# BMS_Practice_Board.net
KiCad netlist of a schematic drawn in EAGLE
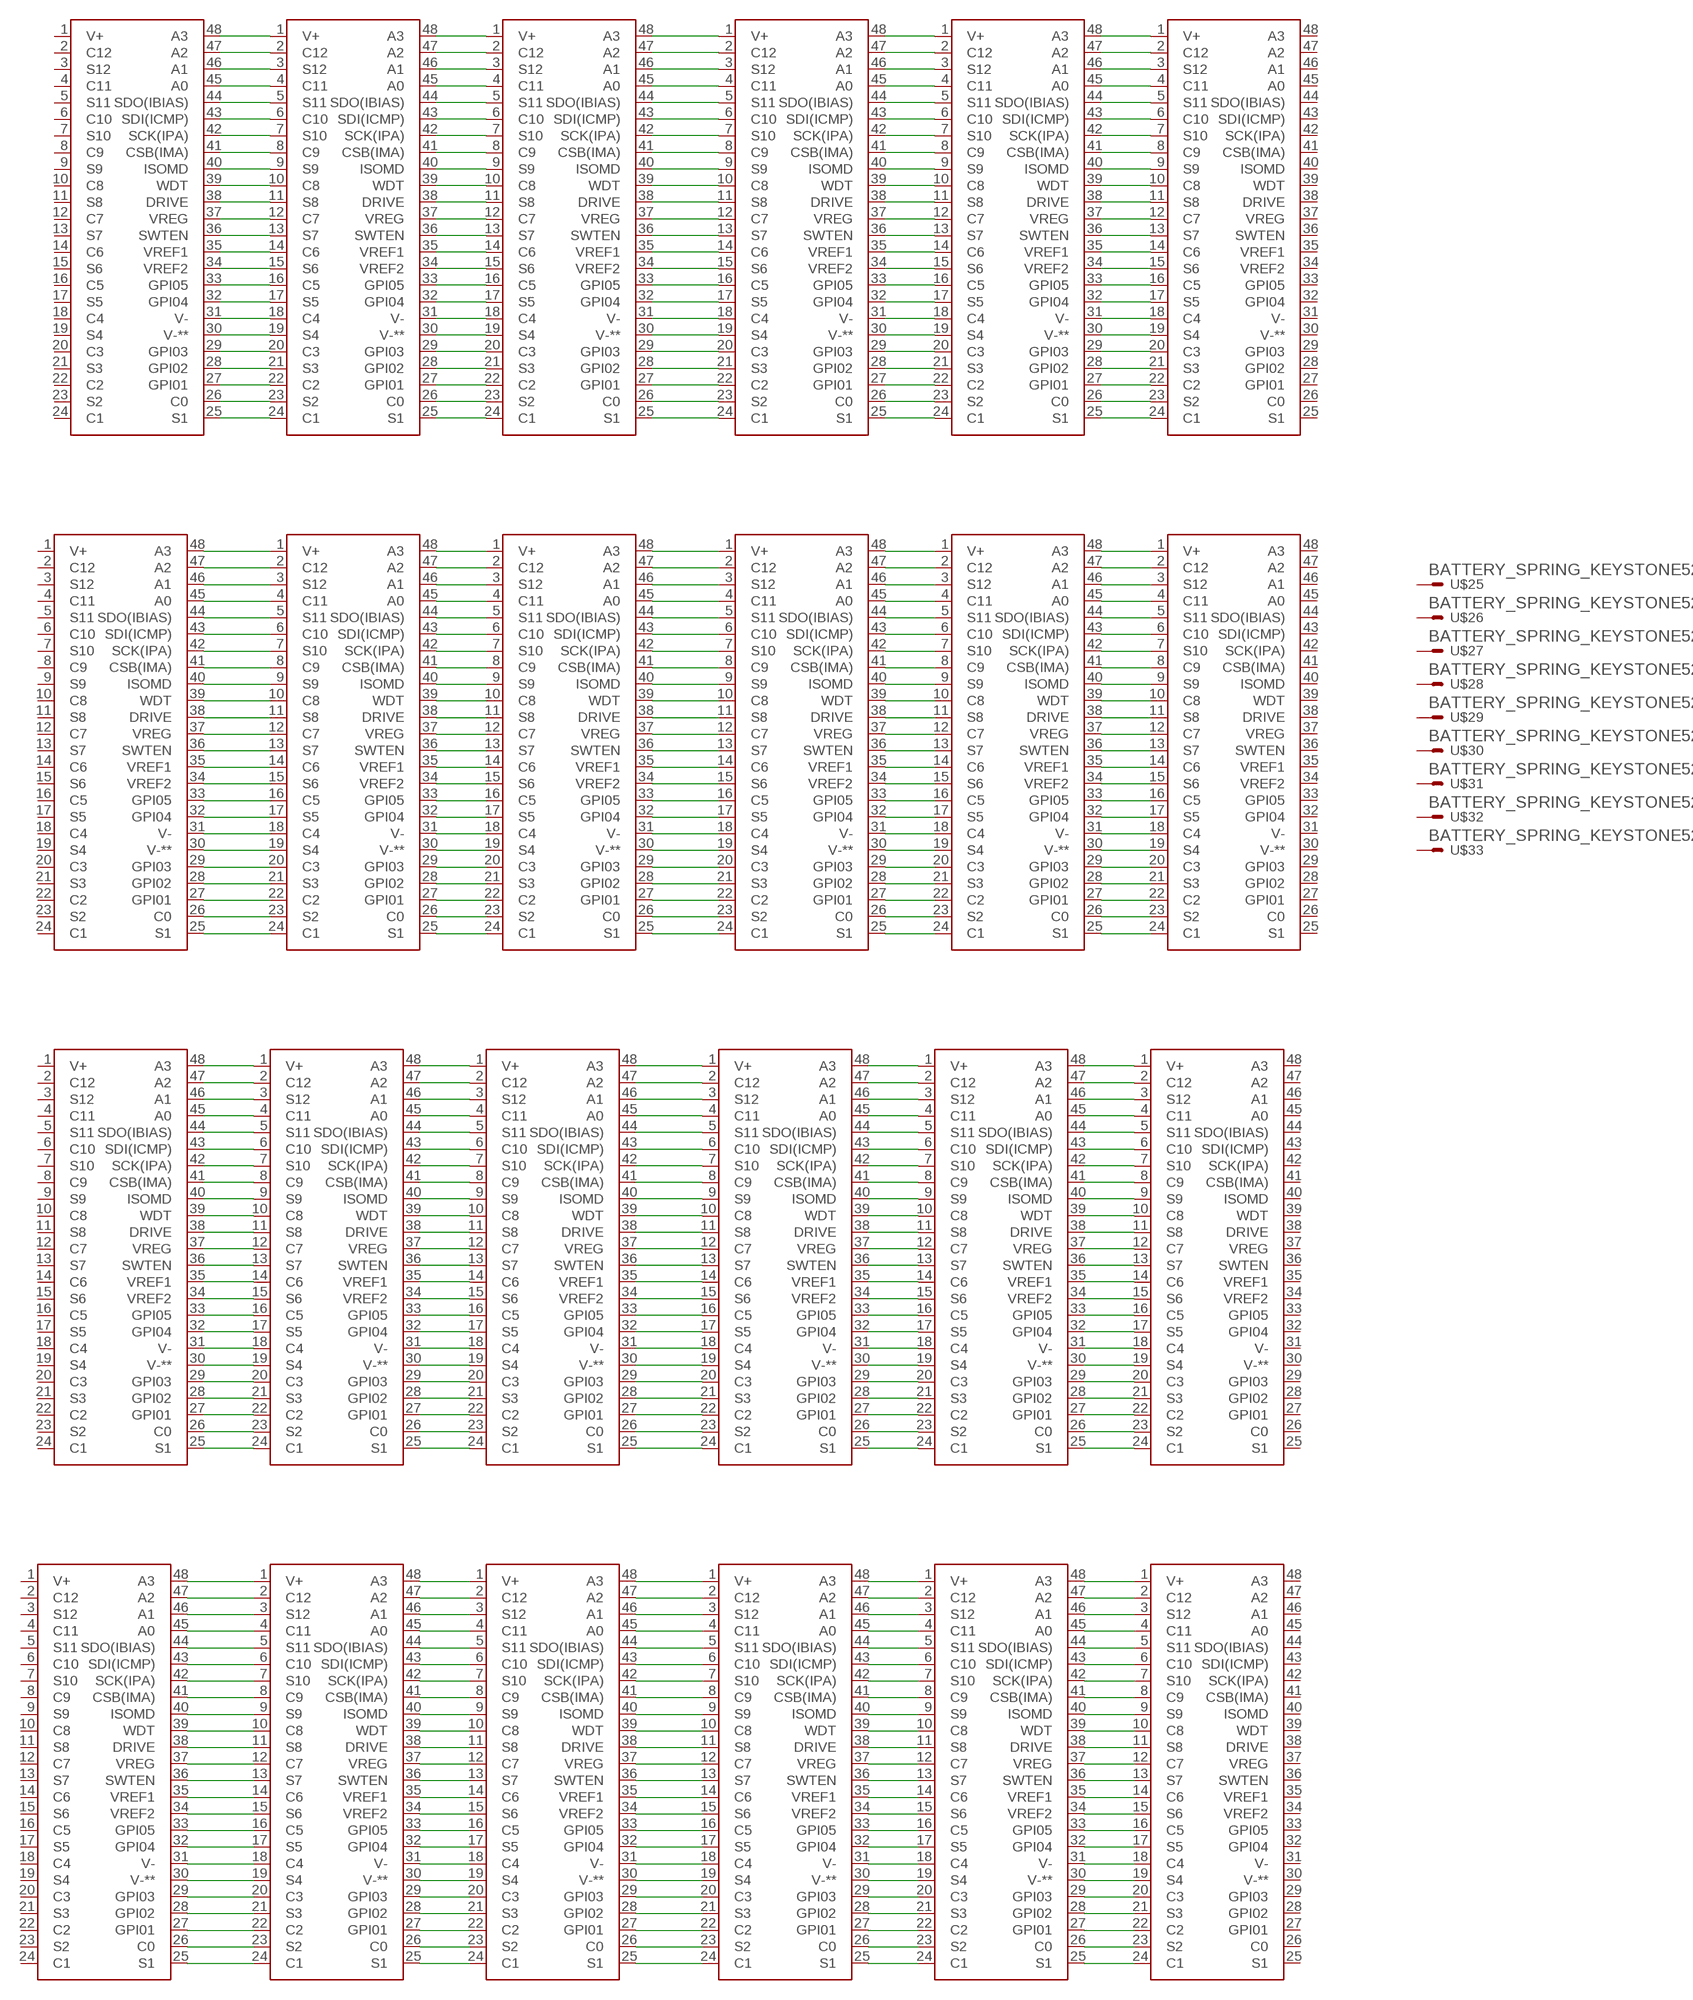
[diagram p0: schematic, sheet 1]

(export (version "E")
  (design (tool "Eeschema 10.0.6"))
  (components
    (comp (ref "U$1")
      (value "LTC6804-2")
      (footprint "eagle-import:LTC6804")
      (libsource (lib "eagle-import") (part "LTC6804-2"))
    )
    (comp (ref "U$2")
      (value "LTC6804-2")
      (footprint "eagle-import:LTC6804")
      (libsource (lib "eagle-import") (part "LTC6804-2"))
    )
    (comp (ref "U$3")
      (value "LTC6804-2")
      (footprint "eagle-import:LTC6804")
      (libsource (lib "eagle-import") (part "LTC6804-2"))
    )
    (comp (ref "U$4")
      (value "LTC6804-2")
      (footprint "eagle-import:LTC6804")
      (libsource (lib "eagle-import") (part "LTC6804-2"))
    )
    (comp (ref "U$5")
      (value "LTC6804-2")
      (footprint "eagle-import:LTC6804")
      (libsource (lib "eagle-import") (part "LTC6804-2"))
    )
    (comp (ref "U$6")
      (value "LTC6804-2")
      (footprint "eagle-import:LTC6804")
      (libsource (lib "eagle-import") (part "LTC6804-2"))
    )
    (comp (ref "U$7")
      (value "LTC6804-2")
      (footprint "eagle-import:LTC6804")
      (libsource (lib "eagle-import") (part "LTC6804-2"))
    )
    (comp (ref "U$8")
      (value "LTC6804-2")
      (footprint "eagle-import:LTC6804")
      (libsource (lib "eagle-import") (part "LTC6804-2"))
    )
    (comp (ref "U$9")
      (value "LTC6804-2")
      (footprint "eagle-import:LTC6804")
      (libsource (lib "eagle-import") (part "LTC6804-2"))
    )
    (comp (ref "U$10")
      (value "LTC6804-2")
      (footprint "eagle-import:LTC6804")
      (libsource (lib "eagle-import") (part "LTC6804-2"))
    )
    (comp (ref "U$11")
      (value "LTC6804-2")
      (footprint "eagle-import:LTC6804")
      (libsource (lib "eagle-import") (part "LTC6804-2"))
    )
    (comp (ref "U$12")
      (value "LTC6804-2")
      (footprint "eagle-import:LTC6804")
      (libsource (lib "eagle-import") (part "LTC6804-2"))
    )
    (comp (ref "U$13")
      (value "LTC6804-2")
      (footprint "eagle-import:LTC6804")
      (libsource (lib "eagle-import") (part "LTC6804-2"))
    )
    (comp (ref "U$14")
      (value "LTC6804-2")
      (footprint "eagle-import:LTC6804")
      (libsource (lib "eagle-import") (part "LTC6804-2"))
    )
    (comp (ref "U$15")
      (value "LTC6804-2")
      (footprint "eagle-import:LTC6804")
      (libsource (lib "eagle-import") (part "LTC6804-2"))
    )
    (comp (ref "U$16")
      (value "LTC6804-2")
      (footprint "eagle-import:LTC6804")
      (libsource (lib "eagle-import") (part "LTC6804-2"))
    )
    (comp (ref "U$17")
      (value "LTC6804-2")
      (footprint "eagle-import:LTC6804")
      (libsource (lib "eagle-import") (part "LTC6804-2"))
    )
    (comp (ref "U$18")
      (value "LTC6804-2")
      (footprint "eagle-import:LTC6804")
      (libsource (lib "eagle-import") (part "LTC6804-2"))
    )
    (comp (ref "U$19")
      (value "LTC6804-2")
      (footprint "eagle-import:LTC6804")
      (libsource (lib "eagle-import") (part "LTC6804-2"))
    )
    (comp (ref "U$20")
      (value "LTC6804-2")
      (footprint "eagle-import:LTC6804")
      (libsource (lib "eagle-import") (part "LTC6804-2"))
    )
    (comp (ref "U$21")
      (value "LTC6804-2")
      (footprint "eagle-import:LTC6804")
      (libsource (lib "eagle-import") (part "LTC6804-2"))
    )
    (comp (ref "U$22")
      (value "LTC6804-2")
      (footprint "eagle-import:LTC6804")
      (libsource (lib "eagle-import") (part "LTC6804-2"))
    )
    (comp (ref "U$23")
      (value "LTC6804-2")
      (footprint "eagle-import:LTC6804")
      (libsource (lib "eagle-import") (part "LTC6804-2"))
    )
    (comp (ref "U$24")
      (value "LTC6804-2")
      (footprint "eagle-import:LTC6804")
      (libsource (lib "eagle-import") (part "LTC6804-2"))
    )
    (comp (ref "U$25")
      (value "BATTERY_SPRING_KEYSTONE5222")
      (footprint "eagle-import:KEYSTONE5222")
      (libsource (lib "eagle-import") (part "BATTERY_SPRING_KEYSTONE5222"))
    )
    (comp (ref "U$26")
      (value "BATTERY_SPRING_KEYSTONE5222")
      (footprint "eagle-import:KEYSTONE5222")
      (libsource (lib "eagle-import") (part "BATTERY_SPRING_KEYSTONE5222"))
    )
    (comp (ref "U$27")
      (value "BATTERY_SPRING_KEYSTONE5222")
      (footprint "eagle-import:KEYSTONE5222")
      (libsource (lib "eagle-import") (part "BATTERY_SPRING_KEYSTONE5222"))
    )
    (comp (ref "U$28")
      (value "BATTERY_SPRING_KEYSTONE5222")
      (footprint "eagle-import:KEYSTONE5222")
      (libsource (lib "eagle-import") (part "BATTERY_SPRING_KEYSTONE5222"))
    )
    (comp (ref "U$29")
      (value "BATTERY_SPRING_KEYSTONE5222")
      (footprint "eagle-import:KEYSTONE5222")
      (libsource (lib "eagle-import") (part "BATTERY_SPRING_KEYSTONE5222"))
    )
    (comp (ref "U$30")
      (value "BATTERY_SPRING_KEYSTONE5222")
      (footprint "eagle-import:KEYSTONE5222")
      (libsource (lib "eagle-import") (part "BATTERY_SPRING_KEYSTONE5222"))
    )
    (comp (ref "U$31")
      (value "BATTERY_SPRING_KEYSTONE5222")
      (footprint "eagle-import:KEYSTONE5222")
      (libsource (lib "eagle-import") (part "BATTERY_SPRING_KEYSTONE5222"))
    )
    (comp (ref "U$32")
      (value "BATTERY_SPRING_KEYSTONE5222")
      (footprint "eagle-import:KEYSTONE5222")
      (libsource (lib "eagle-import") (part "BATTERY_SPRING_KEYSTONE5222"))
    )
    (comp (ref "U$33")
      (value "BATTERY_SPRING_KEYSTONE5222")
      (footprint "eagle-import:KEYSTONE5222")
      (libsource (lib "eagle-import") (part "BATTERY_SPRING_KEYSTONE5222"))
    )
  )
  (nets
    (net (code "1") (name "Net-(U$1-A0)") (class "Default")
      (node (ref "U$1") (pin "45") (pinfunction "A0_45") (pintype "bidirectional"))
      (node (ref "U$2") (pin "4") (pinfunction "C11_4") (pintype "bidirectional"))
    )
    (net (code "2") (name "Net-(U$1-A1)") (class "Default")
      (node (ref "U$1") (pin "46") (pinfunction "A1_46") (pintype "bidirectional"))
      (node (ref "U$2") (pin "3") (pinfunction "S12_3") (pintype "bidirectional"))
    )
    (net (code "3") (name "Net-(U$1-A2)") (class "Default")
      (node (ref "U$1") (pin "47") (pinfunction "A2_47") (pintype "bidirectional"))
      (node (ref "U$2") (pin "2") (pinfunction "C12_2") (pintype "bidirectional"))
    )
    (net (code "4") (name "Net-(U$1-A3)") (class "Default")
      (node (ref "U$1") (pin "48") (pinfunction "A3_48") (pintype "bidirectional"))
      (node (ref "U$2") (pin "1") (pinfunction "V+_1") (pintype "bidirectional"))
    )
    (net (code "5") (name "Net-(U$1-C0)") (class "Default")
      (node (ref "U$1") (pin "26") (pinfunction "C0_26") (pintype "bidirectional"))
      (node (ref "U$2") (pin "23") (pinfunction "S2_23") (pintype "bidirectional"))
    )
    (net (code "6") (name "Net-(U$1-CSB(IMA))") (class "Default")
      (node (ref "U$1") (pin "41") (pinfunction "CSB(IMA)_41") (pintype "bidirectional"))
      (node (ref "U$2") (pin "8") (pinfunction "C9_8") (pintype "bidirectional"))
    )
    (net (code "7") (name "Net-(U$1-DRIVE)") (class "Default")
      (node (ref "U$1") (pin "38") (pinfunction "DRIVE_38") (pintype "bidirectional"))
      (node (ref "U$2") (pin "11") (pinfunction "S8_11") (pintype "bidirectional"))
    )
    (net (code "8") (name "Net-(U$1-GPI01)") (class "Default")
      (node (ref "U$1") (pin "27") (pinfunction "GPI01_27") (pintype "bidirectional"))
      (node (ref "U$2") (pin "22") (pinfunction "C2_22") (pintype "bidirectional"))
    )
    (net (code "9") (name "Net-(U$1-GPI02)") (class "Default")
      (node (ref "U$1") (pin "28") (pinfunction "GPI02_28") (pintype "bidirectional"))
      (node (ref "U$2") (pin "21") (pinfunction "S3_21") (pintype "bidirectional"))
    )
    (net (code "10") (name "Net-(U$1-GPI03)") (class "Default")
      (node (ref "U$1") (pin "29") (pinfunction "GPI03_29") (pintype "bidirectional"))
      (node (ref "U$2") (pin "20") (pinfunction "C3_20") (pintype "bidirectional"))
    )
    (net (code "11") (name "Net-(U$1-GPI04)") (class "Default")
      (node (ref "U$1") (pin "32") (pinfunction "GPI04_32") (pintype "bidirectional"))
      (node (ref "U$2") (pin "17") (pinfunction "S5_17") (pintype "bidirectional"))
    )
    (net (code "12") (name "Net-(U$1-GPI05)") (class "Default")
      (node (ref "U$1") (pin "33") (pinfunction "GPI05_33") (pintype "bidirectional"))
      (node (ref "U$2") (pin "16") (pinfunction "C5_16") (pintype "bidirectional"))
    )
    (net (code "13") (name "Net-(U$1-ISOMD)") (class "Default")
      (node (ref "U$1") (pin "40") (pinfunction "ISOMD_40") (pintype "bidirectional"))
      (node (ref "U$2") (pin "9") (pinfunction "S9_9") (pintype "bidirectional"))
    )
    (net (code "14") (name "Net-(U$1-S1)") (class "Default")
      (node (ref "U$1") (pin "25") (pinfunction "S1_25") (pintype "bidirectional"))
      (node (ref "U$2") (pin "24") (pinfunction "C1_24") (pintype "bidirectional"))
    )
    (net (code "15") (name "Net-(U$1-SCK(IPA))") (class "Default")
      (node (ref "U$1") (pin "42") (pinfunction "SCK(IPA)_42") (pintype "bidirectional"))
      (node (ref "U$2") (pin "7") (pinfunction "S10_7") (pintype "bidirectional"))
    )
    (net (code "16") (name "Net-(U$1-SDI(ICMP))") (class "Default")
      (node (ref "U$1") (pin "43") (pinfunction "SDI(ICMP)_43") (pintype "bidirectional"))
      (node (ref "U$2") (pin "6") (pinfunction "C10_6") (pintype "bidirectional"))
    )
    (net (code "17") (name "Net-(U$1-SDO(IBIAS))") (class "Default")
      (node (ref "U$1") (pin "44") (pinfunction "SDO(IBIAS)_44") (pintype "bidirectional"))
      (node (ref "U$2") (pin "5") (pinfunction "S11_5") (pintype "bidirectional"))
    )
    (net (code "18") (name "Net-(U$1-SWTEN)") (class "Default")
      (node (ref "U$1") (pin "36") (pinfunction "SWTEN_36") (pintype "bidirectional"))
      (node (ref "U$2") (pin "13") (pinfunction "S7_13") (pintype "bidirectional"))
    )
    (net (code "19") (name "Net-(U$1-V-)") (class "Default")
      (node (ref "U$1") (pin "31") (pinfunction "V-_31") (pintype "bidirectional"))
      (node (ref "U$2") (pin "18") (pinfunction "C4_18") (pintype "bidirectional"))
    )
    (net (code "20") (name "Net-(U$1-V-**)") (class "Default")
      (node (ref "U$1") (pin "30") (pinfunction "V-**_30") (pintype "bidirectional"))
      (node (ref "U$2") (pin "19") (pinfunction "S4_19") (pintype "bidirectional"))
    )
    (net (code "21") (name "Net-(U$1-VREF1)") (class "Default")
      (node (ref "U$1") (pin "35") (pinfunction "VREF1_35") (pintype "bidirectional"))
      (node (ref "U$2") (pin "14") (pinfunction "C6_14") (pintype "bidirectional"))
    )
    (net (code "22") (name "Net-(U$1-VREF2)") (class "Default")
      (node (ref "U$1") (pin "34") (pinfunction "VREF2_34") (pintype "bidirectional"))
      (node (ref "U$2") (pin "15") (pinfunction "S6_15") (pintype "bidirectional"))
    )
    (net (code "23") (name "Net-(U$1-VREG)") (class "Default")
      (node (ref "U$1") (pin "37") (pinfunction "VREG_37") (pintype "bidirectional"))
      (node (ref "U$2") (pin "12") (pinfunction "C7_12") (pintype "bidirectional"))
    )
    (net (code "24") (name "Net-(U$1-WDT)") (class "Default")
      (node (ref "U$1") (pin "39") (pinfunction "WDT_39") (pintype "bidirectional"))
      (node (ref "U$2") (pin "10") (pinfunction "C8_10") (pintype "bidirectional"))
    )
    (net (code "25") (name "Net-(U$2-A0)") (class "Default")
      (node (ref "U$2") (pin "45") (pinfunction "A0_45") (pintype "bidirectional"))
      (node (ref "U$3") (pin "4") (pinfunction "C11_4") (pintype "bidirectional"))
    )
    (net (code "26") (name "Net-(U$2-A1)") (class "Default")
      (node (ref "U$2") (pin "46") (pinfunction "A1_46") (pintype "bidirectional"))
      (node (ref "U$3") (pin "3") (pinfunction "S12_3") (pintype "bidirectional"))
    )
    (net (code "27") (name "Net-(U$2-A2)") (class "Default")
      (node (ref "U$2") (pin "47") (pinfunction "A2_47") (pintype "bidirectional"))
      (node (ref "U$3") (pin "2") (pinfunction "C12_2") (pintype "bidirectional"))
    )
    (net (code "28") (name "Net-(U$2-A3)") (class "Default")
      (node (ref "U$2") (pin "48") (pinfunction "A3_48") (pintype "bidirectional"))
      (node (ref "U$3") (pin "1") (pinfunction "V+_1") (pintype "bidirectional"))
    )
    (net (code "29") (name "Net-(U$2-C0)") (class "Default")
      (node (ref "U$2") (pin "26") (pinfunction "C0_26") (pintype "bidirectional"))
      (node (ref "U$3") (pin "23") (pinfunction "S2_23") (pintype "bidirectional"))
    )
    (net (code "30") (name "Net-(U$2-CSB(IMA))") (class "Default")
      (node (ref "U$2") (pin "41") (pinfunction "CSB(IMA)_41") (pintype "bidirectional"))
      (node (ref "U$3") (pin "8") (pinfunction "C9_8") (pintype "bidirectional"))
    )
    (net (code "31") (name "Net-(U$2-DRIVE)") (class "Default")
      (node (ref "U$2") (pin "38") (pinfunction "DRIVE_38") (pintype "bidirectional"))
      (node (ref "U$3") (pin "11") (pinfunction "S8_11") (pintype "bidirectional"))
    )
    (net (code "32") (name "Net-(U$2-GPI01)") (class "Default")
      (node (ref "U$2") (pin "27") (pinfunction "GPI01_27") (pintype "bidirectional"))
      (node (ref "U$3") (pin "22") (pinfunction "C2_22") (pintype "bidirectional"))
    )
    (net (code "33") (name "Net-(U$2-GPI02)") (class "Default")
      (node (ref "U$2") (pin "28") (pinfunction "GPI02_28") (pintype "bidirectional"))
      (node (ref "U$3") (pin "21") (pinfunction "S3_21") (pintype "bidirectional"))
    )
    (net (code "34") (name "Net-(U$2-GPI03)") (class "Default")
      (node (ref "U$2") (pin "29") (pinfunction "GPI03_29") (pintype "bidirectional"))
      (node (ref "U$3") (pin "20") (pinfunction "C3_20") (pintype "bidirectional"))
    )
    (net (code "35") (name "Net-(U$2-GPI04)") (class "Default")
      (node (ref "U$2") (pin "32") (pinfunction "GPI04_32") (pintype "bidirectional"))
      (node (ref "U$3") (pin "17") (pinfunction "S5_17") (pintype "bidirectional"))
    )
    (net (code "36") (name "Net-(U$2-GPI05)") (class "Default")
      (node (ref "U$2") (pin "33") (pinfunction "GPI05_33") (pintype "bidirectional"))
      (node (ref "U$3") (pin "16") (pinfunction "C5_16") (pintype "bidirectional"))
    )
    (net (code "37") (name "Net-(U$2-ISOMD)") (class "Default")
      (node (ref "U$2") (pin "40") (pinfunction "ISOMD_40") (pintype "bidirectional"))
      (node (ref "U$3") (pin "9") (pinfunction "S9_9") (pintype "bidirectional"))
    )
    (net (code "38") (name "Net-(U$2-S1)") (class "Default")
      (node (ref "U$2") (pin "25") (pinfunction "S1_25") (pintype "bidirectional"))
      (node (ref "U$3") (pin "24") (pinfunction "C1_24") (pintype "bidirectional"))
    )
    (net (code "39") (name "Net-(U$2-SCK(IPA))") (class "Default")
      (node (ref "U$2") (pin "42") (pinfunction "SCK(IPA)_42") (pintype "bidirectional"))
      (node (ref "U$3") (pin "7") (pinfunction "S10_7") (pintype "bidirectional"))
    )
    (net (code "40") (name "Net-(U$2-SDI(ICMP))") (class "Default")
      (node (ref "U$2") (pin "43") (pinfunction "SDI(ICMP)_43") (pintype "bidirectional"))
      (node (ref "U$3") (pin "6") (pinfunction "C10_6") (pintype "bidirectional"))
    )
    (net (code "41") (name "Net-(U$2-SDO(IBIAS))") (class "Default")
      (node (ref "U$2") (pin "44") (pinfunction "SDO(IBIAS)_44") (pintype "bidirectional"))
      (node (ref "U$3") (pin "5") (pinfunction "S11_5") (pintype "bidirectional"))
    )
    (net (code "42") (name "Net-(U$2-SWTEN)") (class "Default")
      (node (ref "U$2") (pin "36") (pinfunction "SWTEN_36") (pintype "bidirectional"))
      (node (ref "U$3") (pin "13") (pinfunction "S7_13") (pintype "bidirectional"))
    )
    (net (code "43") (name "Net-(U$2-V-)") (class "Default")
      (node (ref "U$2") (pin "31") (pinfunction "V-_31") (pintype "bidirectional"))
      (node (ref "U$3") (pin "18") (pinfunction "C4_18") (pintype "bidirectional"))
    )
    (net (code "44") (name "Net-(U$2-V-**)") (class "Default")
      (node (ref "U$2") (pin "30") (pinfunction "V-**_30") (pintype "bidirectional"))
      (node (ref "U$3") (pin "19") (pinfunction "S4_19") (pintype "bidirectional"))
    )
    (net (code "45") (name "Net-(U$2-VREF1)") (class "Default")
      (node (ref "U$2") (pin "35") (pinfunction "VREF1_35") (pintype "bidirectional"))
      (node (ref "U$3") (pin "14") (pinfunction "C6_14") (pintype "bidirectional"))
    )
    (net (code "46") (name "Net-(U$2-VREF2)") (class "Default")
      (node (ref "U$2") (pin "34") (pinfunction "VREF2_34") (pintype "bidirectional"))
      (node (ref "U$3") (pin "15") (pinfunction "S6_15") (pintype "bidirectional"))
    )
    (net (code "47") (name "Net-(U$2-VREG)") (class "Default")
      (node (ref "U$2") (pin "37") (pinfunction "VREG_37") (pintype "bidirectional"))
      (node (ref "U$3") (pin "12") (pinfunction "C7_12") (pintype "bidirectional"))
    )
    (net (code "48") (name "Net-(U$2-WDT)") (class "Default")
      (node (ref "U$2") (pin "39") (pinfunction "WDT_39") (pintype "bidirectional"))
      (node (ref "U$3") (pin "10") (pinfunction "C8_10") (pintype "bidirectional"))
    )
    (net (code "49") (name "Net-(U$3-A0)") (class "Default")
      (node (ref "U$3") (pin "45") (pinfunction "A0_45") (pintype "bidirectional"))
      (node (ref "U$4") (pin "4") (pinfunction "C11_4") (pintype "bidirectional"))
    )
    (net (code "50") (name "Net-(U$3-A1)") (class "Default")
      (node (ref "U$3") (pin "46") (pinfunction "A1_46") (pintype "bidirectional"))
      (node (ref "U$4") (pin "3") (pinfunction "S12_3") (pintype "bidirectional"))
    )
    (net (code "51") (name "Net-(U$3-A2)") (class "Default")
      (node (ref "U$3") (pin "47") (pinfunction "A2_47") (pintype "bidirectional"))
      (node (ref "U$4") (pin "2") (pinfunction "C12_2") (pintype "bidirectional"))
    )
    (net (code "52") (name "Net-(U$3-A3)") (class "Default")
      (node (ref "U$3") (pin "48") (pinfunction "A3_48") (pintype "bidirectional"))
      (node (ref "U$4") (pin "1") (pinfunction "V+_1") (pintype "bidirectional"))
    )
    (net (code "53") (name "Net-(U$3-C0)") (class "Default")
      (node (ref "U$3") (pin "26") (pinfunction "C0_26") (pintype "bidirectional"))
      (node (ref "U$4") (pin "23") (pinfunction "S2_23") (pintype "bidirectional"))
    )
    (net (code "54") (name "Net-(U$3-CSB(IMA))") (class "Default")
      (node (ref "U$3") (pin "41") (pinfunction "CSB(IMA)_41") (pintype "bidirectional"))
      (node (ref "U$4") (pin "8") (pinfunction "C9_8") (pintype "bidirectional"))
    )
    (net (code "55") (name "Net-(U$3-DRIVE)") (class "Default")
      (node (ref "U$3") (pin "38") (pinfunction "DRIVE_38") (pintype "bidirectional"))
      (node (ref "U$4") (pin "11") (pinfunction "S8_11") (pintype "bidirectional"))
    )
    (net (code "56") (name "Net-(U$3-GPI01)") (class "Default")
      (node (ref "U$3") (pin "27") (pinfunction "GPI01_27") (pintype "bidirectional"))
      (node (ref "U$4") (pin "22") (pinfunction "C2_22") (pintype "bidirectional"))
    )
    (net (code "57") (name "Net-(U$3-GPI02)") (class "Default")
      (node (ref "U$3") (pin "28") (pinfunction "GPI02_28") (pintype "bidirectional"))
      (node (ref "U$4") (pin "21") (pinfunction "S3_21") (pintype "bidirectional"))
    )
    (net (code "58") (name "Net-(U$3-GPI03)") (class "Default")
      (node (ref "U$3") (pin "29") (pinfunction "GPI03_29") (pintype "bidirectional"))
      (node (ref "U$4") (pin "20") (pinfunction "C3_20") (pintype "bidirectional"))
    )
    (net (code "59") (name "Net-(U$3-GPI04)") (class "Default")
      (node (ref "U$3") (pin "32") (pinfunction "GPI04_32") (pintype "bidirectional"))
      (node (ref "U$4") (pin "17") (pinfunction "S5_17") (pintype "bidirectional"))
    )
    (net (code "60") (name "Net-(U$3-GPI05)") (class "Default")
      (node (ref "U$3") (pin "33") (pinfunction "GPI05_33") (pintype "bidirectional"))
      (node (ref "U$4") (pin "16") (pinfunction "C5_16") (pintype "bidirectional"))
    )
    (net (code "61") (name "Net-(U$3-ISOMD)") (class "Default")
      (node (ref "U$3") (pin "40") (pinfunction "ISOMD_40") (pintype "bidirectional"))
      (node (ref "U$4") (pin "9") (pinfunction "S9_9") (pintype "bidirectional"))
    )
    (net (code "62") (name "Net-(U$3-S1)") (class "Default")
      (node (ref "U$3") (pin "25") (pinfunction "S1_25") (pintype "bidirectional"))
      (node (ref "U$4") (pin "24") (pinfunction "C1_24") (pintype "bidirectional"))
    )
    (net (code "63") (name "Net-(U$3-SCK(IPA))") (class "Default")
      (node (ref "U$3") (pin "42") (pinfunction "SCK(IPA)_42") (pintype "bidirectional"))
      (node (ref "U$4") (pin "7") (pinfunction "S10_7") (pintype "bidirectional"))
    )
    (net (code "64") (name "Net-(U$3-SDI(ICMP))") (class "Default")
      (node (ref "U$3") (pin "43") (pinfunction "SDI(ICMP)_43") (pintype "bidirectional"))
      (node (ref "U$4") (pin "6") (pinfunction "C10_6") (pintype "bidirectional"))
    )
    (net (code "65") (name "Net-(U$3-SDO(IBIAS))") (class "Default")
      (node (ref "U$3") (pin "44") (pinfunction "SDO(IBIAS)_44") (pintype "bidirectional"))
      (node (ref "U$4") (pin "5") (pinfunction "S11_5") (pintype "bidirectional"))
    )
    (net (code "66") (name "Net-(U$3-SWTEN)") (class "Default")
      (node (ref "U$3") (pin "36") (pinfunction "SWTEN_36") (pintype "bidirectional"))
      (node (ref "U$4") (pin "13") (pinfunction "S7_13") (pintype "bidirectional"))
    )
    (net (code "67") (name "Net-(U$3-V-)") (class "Default")
      (node (ref "U$3") (pin "31") (pinfunction "V-_31") (pintype "bidirectional"))
      (node (ref "U$4") (pin "18") (pinfunction "C4_18") (pintype "bidirectional"))
    )
    (net (code "68") (name "Net-(U$3-V-**)") (class "Default")
      (node (ref "U$3") (pin "30") (pinfunction "V-**_30") (pintype "bidirectional"))
      (node (ref "U$4") (pin "19") (pinfunction "S4_19") (pintype "bidirectional"))
    )
    (net (code "69") (name "Net-(U$3-VREF1)") (class "Default")
      (node (ref "U$3") (pin "35") (pinfunction "VREF1_35") (pintype "bidirectional"))
      (node (ref "U$4") (pin "14") (pinfunction "C6_14") (pintype "bidirectional"))
    )
    (net (code "70") (name "Net-(U$3-VREF2)") (class "Default")
      (node (ref "U$3") (pin "34") (pinfunction "VREF2_34") (pintype "bidirectional"))
      (node (ref "U$4") (pin "15") (pinfunction "S6_15") (pintype "bidirectional"))
    )
    (net (code "71") (name "Net-(U$3-VREG)") (class "Default")
      (node (ref "U$3") (pin "37") (pinfunction "VREG_37") (pintype "bidirectional"))
      (node (ref "U$4") (pin "12") (pinfunction "C7_12") (pintype "bidirectional"))
    )
    (net (code "72") (name "Net-(U$3-WDT)") (class "Default")
      (node (ref "U$3") (pin "39") (pinfunction "WDT_39") (pintype "bidirectional"))
      (node (ref "U$4") (pin "10") (pinfunction "C8_10") (pintype "bidirectional"))
    )
    (net (code "73") (name "Net-(U$4-A0)") (class "Default")
      (node (ref "U$4") (pin "45") (pinfunction "A0_45") (pintype "bidirectional"))
      (node (ref "U$5") (pin "4") (pinfunction "C11_4") (pintype "bidirectional"))
    )
    (net (code "74") (name "Net-(U$4-A1)") (class "Default")
      (node (ref "U$4") (pin "46") (pinfunction "A1_46") (pintype "bidirectional"))
      (node (ref "U$5") (pin "3") (pinfunction "S12_3") (pintype "bidirectional"))
    )
    (net (code "75") (name "Net-(U$4-A2)") (class "Default")
      (node (ref "U$4") (pin "47") (pinfunction "A2_47") (pintype "bidirectional"))
      (node (ref "U$5") (pin "2") (pinfunction "C12_2") (pintype "bidirectional"))
    )
    (net (code "76") (name "Net-(U$4-A3)") (class "Default")
      (node (ref "U$4") (pin "48") (pinfunction "A3_48") (pintype "bidirectional"))
      (node (ref "U$5") (pin "1") (pinfunction "V+_1") (pintype "bidirectional"))
    )
    (net (code "77") (name "Net-(U$4-C0)") (class "Default")
      (node (ref "U$4") (pin "26") (pinfunction "C0_26") (pintype "bidirectional"))
      (node (ref "U$5") (pin "23") (pinfunction "S2_23") (pintype "bidirectional"))
    )
    (net (code "78") (name "Net-(U$4-CSB(IMA))") (class "Default")
      (node (ref "U$4") (pin "41") (pinfunction "CSB(IMA)_41") (pintype "bidirectional"))
      (node (ref "U$5") (pin "8") (pinfunction "C9_8") (pintype "bidirectional"))
    )
    (net (code "79") (name "Net-(U$4-DRIVE)") (class "Default")
      (node (ref "U$4") (pin "38") (pinfunction "DRIVE_38") (pintype "bidirectional"))
      (node (ref "U$5") (pin "11") (pinfunction "S8_11") (pintype "bidirectional"))
    )
    (net (code "80") (name "Net-(U$4-GPI01)") (class "Default")
      (node (ref "U$4") (pin "27") (pinfunction "GPI01_27") (pintype "bidirectional"))
      (node (ref "U$5") (pin "22") (pinfunction "C2_22") (pintype "bidirectional"))
    )
    (net (code "81") (name "Net-(U$4-GPI02)") (class "Default")
      (node (ref "U$4") (pin "28") (pinfunction "GPI02_28") (pintype "bidirectional"))
      (node (ref "U$5") (pin "21") (pinfunction "S3_21") (pintype "bidirectional"))
    )
    (net (code "82") (name "Net-(U$4-GPI03)") (class "Default")
      (node (ref "U$4") (pin "29") (pinfunction "GPI03_29") (pintype "bidirectional"))
      (node (ref "U$5") (pin "20") (pinfunction "C3_20") (pintype "bidirectional"))
    )
    (net (code "83") (name "Net-(U$4-GPI04)") (class "Default")
      (node (ref "U$4") (pin "32") (pinfunction "GPI04_32") (pintype "bidirectional"))
      (node (ref "U$5") (pin "17") (pinfunction "S5_17") (pintype "bidirectional"))
    )
    (net (code "84") (name "Net-(U$4-GPI05)") (class "Default")
      (node (ref "U$4") (pin "33") (pinfunction "GPI05_33") (pintype "bidirectional"))
      (node (ref "U$5") (pin "16") (pinfunction "C5_16") (pintype "bidirectional"))
    )
    (net (code "85") (name "Net-(U$4-ISOMD)") (class "Default")
      (node (ref "U$4") (pin "40") (pinfunction "ISOMD_40") (pintype "bidirectional"))
      (node (ref "U$5") (pin "9") (pinfunction "S9_9") (pintype "bidirectional"))
    )
    (net (code "86") (name "Net-(U$4-S1)") (class "Default")
      (node (ref "U$4") (pin "25") (pinfunction "S1_25") (pintype "bidirectional"))
      (node (ref "U$5") (pin "24") (pinfunction "C1_24") (pintype "bidirectional"))
    )
    (net (code "87") (name "Net-(U$4-SCK(IPA))") (class "Default")
      (node (ref "U$4") (pin "42") (pinfunction "SCK(IPA)_42") (pintype "bidirectional"))
      (node (ref "U$5") (pin "7") (pinfunction "S10_7") (pintype "bidirectional"))
    )
    (net (code "88") (name "Net-(U$4-SDI(ICMP))") (class "Default")
      (node (ref "U$4") (pin "43") (pinfunction "SDI(ICMP)_43") (pintype "bidirectional"))
      (node (ref "U$5") (pin "6") (pinfunction "C10_6") (pintype "bidirectional"))
    )
    (net (code "89") (name "Net-(U$4-SDO(IBIAS))") (class "Default")
      (node (ref "U$4") (pin "44") (pinfunction "SDO(IBIAS)_44") (pintype "bidirectional"))
      (node (ref "U$5") (pin "5") (pinfunction "S11_5") (pintype "bidirectional"))
    )
    (net (code "90") (name "Net-(U$4-SWTEN)") (class "Default")
      (node (ref "U$4") (pin "36") (pinfunction "SWTEN_36") (pintype "bidirectional"))
      (node (ref "U$5") (pin "13") (pinfunction "S7_13") (pintype "bidirectional"))
    )
    (net (code "91") (name "Net-(U$4-V-)") (class "Default")
      (node (ref "U$4") (pin "31") (pinfunction "V-_31") (pintype "bidirectional"))
      (node (ref "U$5") (pin "18") (pinfunction "C4_18") (pintype "bidirectional"))
    )
    (net (code "92") (name "Net-(U$4-V-**)") (class "Default")
      (node (ref "U$4") (pin "30") (pinfunction "V-**_30") (pintype "bidirectional"))
      (node (ref "U$5") (pin "19") (pinfunction "S4_19") (pintype "bidirectional"))
    )
    (net (code "93") (name "Net-(U$4-VREF1)") (class "Default")
      (node (ref "U$4") (pin "35") (pinfunction "VREF1_35") (pintype "bidirectional"))
      (node (ref "U$5") (pin "14") (pinfunction "C6_14") (pintype "bidirectional"))
    )
    (net (code "94") (name "Net-(U$4-VREF2)") (class "Default")
      (node (ref "U$4") (pin "34") (pinfunction "VREF2_34") (pintype "bidirectional"))
      (node (ref "U$5") (pin "15") (pinfunction "S6_15") (pintype "bidirectional"))
    )
    (net (code "95") (name "Net-(U$4-VREG)") (class "Default")
      (node (ref "U$4") (pin "37") (pinfunction "VREG_37") (pintype "bidirectional"))
      (node (ref "U$5") (pin "12") (pinfunction "C7_12") (pintype "bidirectional"))
    )
    (net (code "96") (name "Net-(U$4-WDT)") (class "Default")
      (node (ref "U$4") (pin "39") (pinfunction "WDT_39") (pintype "bidirectional"))
      (node (ref "U$5") (pin "10") (pinfunction "C8_10") (pintype "bidirectional"))
    )
    (net (code "97") (name "Net-(U$5-A0)") (class "Default")
      (node (ref "U$5") (pin "45") (pinfunction "A0_45") (pintype "bidirectional"))
      (node (ref "U$6") (pin "4") (pinfunction "C11_4") (pintype "bidirectional"))
    )
    (net (code "98") (name "Net-(U$5-A1)") (class "Default")
      (node (ref "U$5") (pin "46") (pinfunction "A1_46") (pintype "bidirectional"))
      (node (ref "U$6") (pin "3") (pinfunction "S12_3") (pintype "bidirectional"))
    )
    (net (code "99") (name "Net-(U$5-A2)") (class "Default")
      (node (ref "U$5") (pin "47") (pinfunction "A2_47") (pintype "bidirectional"))
      (node (ref "U$6") (pin "2") (pinfunction "C12_2") (pintype "bidirectional"))
    )
    (net (code "100") (name "Net-(U$5-A3)") (class "Default")
      (node (ref "U$5") (pin "48") (pinfunction "A3_48") (pintype "bidirectional"))
      (node (ref "U$6") (pin "1") (pinfunction "V+_1") (pintype "bidirectional"))
    )
    (net (code "101") (name "Net-(U$5-C0)") (class "Default")
      (node (ref "U$5") (pin "26") (pinfunction "C0_26") (pintype "bidirectional"))
      (node (ref "U$6") (pin "23") (pinfunction "S2_23") (pintype "bidirectional"))
    )
    (net (code "102") (name "Net-(U$5-CSB(IMA))") (class "Default")
      (node (ref "U$5") (pin "41") (pinfunction "CSB(IMA)_41") (pintype "bidirectional"))
      (node (ref "U$6") (pin "8") (pinfunction "C9_8") (pintype "bidirectional"))
    )
    (net (code "103") (name "Net-(U$5-DRIVE)") (class "Default")
      (node (ref "U$5") (pin "38") (pinfunction "DRIVE_38") (pintype "bidirectional"))
      (node (ref "U$6") (pin "11") (pinfunction "S8_11") (pintype "bidirectional"))
    )
    (net (code "104") (name "Net-(U$5-GPI01)") (class "Default")
      (node (ref "U$5") (pin "27") (pinfunction "GPI01_27") (pintype "bidirectional"))
      (node (ref "U$6") (pin "22") (pinfunction "C2_22") (pintype "bidirectional"))
    )
    (net (code "105") (name "Net-(U$5-GPI02)") (class "Default")
      (node (ref "U$5") (pin "28") (pinfunction "GPI02_28") (pintype "bidirectional"))
      (node (ref "U$6") (pin "21") (pinfunction "S3_21") (pintype "bidirectional"))
    )
    (net (code "106") (name "Net-(U$5-GPI03)") (class "Default")
      (node (ref "U$5") (pin "29") (pinfunction "GPI03_29") (pintype "bidirectional"))
      (node (ref "U$6") (pin "20") (pinfunction "C3_20") (pintype "bidirectional"))
    )
    (net (code "107") (name "Net-(U$5-GPI04)") (class "Default")
      (node (ref "U$5") (pin "32") (pinfunction "GPI04_32") (pintype "bidirectional"))
      (node (ref "U$6") (pin "17") (pinfunction "S5_17") (pintype "bidirectional"))
    )
    (net (code "108") (name "Net-(U$5-GPI05)") (class "Default")
      (node (ref "U$5") (pin "33") (pinfunction "GPI05_33") (pintype "bidirectional"))
      (node (ref "U$6") (pin "16") (pinfunction "C5_16") (pintype "bidirectional"))
    )
    (net (code "109") (name "Net-(U$5-ISOMD)") (class "Default")
      (node (ref "U$5") (pin "40") (pinfunction "ISOMD_40") (pintype "bidirectional"))
      (node (ref "U$6") (pin "9") (pinfunction "S9_9") (pintype "bidirectional"))
    )
    (net (code "110") (name "Net-(U$5-S1)") (class "Default")
      (node (ref "U$5") (pin "25") (pinfunction "S1_25") (pintype "bidirectional"))
      (node (ref "U$6") (pin "24") (pinfunction "C1_24") (pintype "bidirectional"))
    )
    (net (code "111") (name "Net-(U$5-SCK(IPA))") (class "Default")
      (node (ref "U$5") (pin "42") (pinfunction "SCK(IPA)_42") (pintype "bidirectional"))
      (node (ref "U$6") (pin "7") (pinfunction "S10_7") (pintype "bidirectional"))
    )
    (net (code "112") (name "Net-(U$5-SDI(ICMP))") (class "Default")
      (node (ref "U$5") (pin "43") (pinfunction "SDI(ICMP)_43") (pintype "bidirectional"))
      (node (ref "U$6") (pin "6") (pinfunction "C10_6") (pintype "bidirectional"))
    )
    (net (code "113") (name "Net-(U$5-SDO(IBIAS))") (class "Default")
      (node (ref "U$5") (pin "44") (pinfunction "SDO(IBIAS)_44") (pintype "bidirectional"))
      (node (ref "U$6") (pin "5") (pinfunction "S11_5") (pintype "bidirectional"))
    )
    (net (code "114") (name "Net-(U$5-SWTEN)") (class "Default")
      (node (ref "U$5") (pin "36") (pinfunction "SWTEN_36") (pintype "bidirectional"))
      (node (ref "U$6") (pin "13") (pinfunction "S7_13") (pintype "bidirectional"))
    )
    (net (code "115") (name "Net-(U$5-V-)") (class "Default")
      (node (ref "U$5") (pin "31") (pinfunction "V-_31") (pintype "bidirectional"))
      (node (ref "U$6") (pin "18") (pinfunction "C4_18") (pintype "bidirectional"))
    )
    (net (code "116") (name "Net-(U$5-V-**)") (class "Default")
      (node (ref "U$5") (pin "30") (pinfunction "V-**_30") (pintype "bidirectional"))
      (node (ref "U$6") (pin "19") (pinfunction "S4_19") (pintype "bidirectional"))
    )
    (net (code "117") (name "Net-(U$5-VREF1)") (class "Default")
      (node (ref "U$5") (pin "35") (pinfunction "VREF1_35") (pintype "bidirectional"))
      (node (ref "U$6") (pin "14") (pinfunction "C6_14") (pintype "bidirectional"))
    )
    (net (code "118") (name "Net-(U$5-VREF2)") (class "Default")
      (node (ref "U$5") (pin "34") (pinfunction "VREF2_34") (pintype "bidirectional"))
      (node (ref "U$6") (pin "15") (pinfunction "S6_15") (pintype "bidirectional"))
    )
    (net (code "119") (name "Net-(U$5-VREG)") (class "Default")
      (node (ref "U$5") (pin "37") (pinfunction "VREG_37") (pintype "bidirectional"))
      (node (ref "U$6") (pin "12") (pinfunction "C7_12") (pintype "bidirectional"))
    )
    (net (code "120") (name "Net-(U$5-WDT)") (class "Default")
      (node (ref "U$5") (pin "39") (pinfunction "WDT_39") (pintype "bidirectional"))
      (node (ref "U$6") (pin "10") (pinfunction "C8_10") (pintype "bidirectional"))
    )
    (net (code "121") (name "Net-(U$7-A0)") (class "Default")
      (node (ref "U$7") (pin "45") (pinfunction "A0_45") (pintype "bidirectional"))
      (node (ref "U$8") (pin "4") (pinfunction "C11_4") (pintype "bidirectional"))
    )
    (net (code "122") (name "Net-(U$7-A1)") (class "Default")
      (node (ref "U$7") (pin "46") (pinfunction "A1_46") (pintype "bidirectional"))
      (node (ref "U$8") (pin "3") (pinfunction "S12_3") (pintype "bidirectional"))
    )
    (net (code "123") (name "Net-(U$7-A2)") (class "Default")
      (node (ref "U$7") (pin "47") (pinfunction "A2_47") (pintype "bidirectional"))
      (node (ref "U$8") (pin "2") (pinfunction "C12_2") (pintype "bidirectional"))
    )
    (net (code "124") (name "Net-(U$7-A3)") (class "Default")
      (node (ref "U$7") (pin "48") (pinfunction "A3_48") (pintype "bidirectional"))
      (node (ref "U$8") (pin "1") (pinfunction "V+_1") (pintype "bidirectional"))
    )
    (net (code "125") (name "Net-(U$7-C0)") (class "Default")
      (node (ref "U$7") (pin "26") (pinfunction "C0_26") (pintype "bidirectional"))
      (node (ref "U$8") (pin "23") (pinfunction "S2_23") (pintype "bidirectional"))
    )
    (net (code "126") (name "Net-(U$7-CSB(IMA))") (class "Default")
      (node (ref "U$7") (pin "41") (pinfunction "CSB(IMA)_41") (pintype "bidirectional"))
      (node (ref "U$8") (pin "8") (pinfunction "C9_8") (pintype "bidirectional"))
    )
    (net (code "127") (name "Net-(U$7-DRIVE)") (class "Default")
      (node (ref "U$7") (pin "38") (pinfunction "DRIVE_38") (pintype "bidirectional"))
      (node (ref "U$8") (pin "11") (pinfunction "S8_11") (pintype "bidirectional"))
    )
    (net (code "128") (name "Net-(U$7-GPI01)") (class "Default")
      (node (ref "U$7") (pin "27") (pinfunction "GPI01_27") (pintype "bidirectional"))
      (node (ref "U$8") (pin "22") (pinfunction "C2_22") (pintype "bidirectional"))
    )
    (net (code "129") (name "Net-(U$7-GPI02)") (class "Default")
      (node (ref "U$7") (pin "28") (pinfunction "GPI02_28") (pintype "bidirectional"))
      (node (ref "U$8") (pin "21") (pinfunction "S3_21") (pintype "bidirectional"))
    )
    (net (code "130") (name "Net-(U$7-GPI03)") (class "Default")
      (node (ref "U$7") (pin "29") (pinfunction "GPI03_29") (pintype "bidirectional"))
      (node (ref "U$8") (pin "20") (pinfunction "C3_20") (pintype "bidirectional"))
    )
    (net (code "131") (name "Net-(U$7-GPI04)") (class "Default")
      (node (ref "U$7") (pin "32") (pinfunction "GPI04_32") (pintype "bidirectional"))
      (node (ref "U$8") (pin "17") (pinfunction "S5_17") (pintype "bidirectional"))
    )
    (net (code "132") (name "Net-(U$7-GPI05)") (class "Default")
      (node (ref "U$7") (pin "33") (pinfunction "GPI05_33") (pintype "bidirectional"))
      (node (ref "U$8") (pin "16") (pinfunction "C5_16") (pintype "bidirectional"))
    )
    (net (code "133") (name "Net-(U$7-ISOMD)") (class "Default")
      (node (ref "U$7") (pin "40") (pinfunction "ISOMD_40") (pintype "bidirectional"))
      (node (ref "U$8") (pin "9") (pinfunction "S9_9") (pintype "bidirectional"))
    )
    (net (code "134") (name "Net-(U$7-S1)") (class "Default")
      (node (ref "U$7") (pin "25") (pinfunction "S1_25") (pintype "bidirectional"))
      (node (ref "U$8") (pin "24") (pinfunction "C1_24") (pintype "bidirectional"))
    )
    (net (code "135") (name "Net-(U$7-SCK(IPA))") (class "Default")
      (node (ref "U$7") (pin "42") (pinfunction "SCK(IPA)_42") (pintype "bidirectional"))
      (node (ref "U$8") (pin "7") (pinfunction "S10_7") (pintype "bidirectional"))
    )
    (net (code "136") (name "Net-(U$7-SDI(ICMP))") (class "Default")
      (node (ref "U$7") (pin "43") (pinfunction "SDI(ICMP)_43") (pintype "bidirectional"))
      (node (ref "U$8") (pin "6") (pinfunction "C10_6") (pintype "bidirectional"))
    )
    (net (code "137") (name "Net-(U$7-SDO(IBIAS))") (class "Default")
      (node (ref "U$7") (pin "44") (pinfunction "SDO(IBIAS)_44") (pintype "bidirectional"))
      (node (ref "U$8") (pin "5") (pinfunction "S11_5") (pintype "bidirectional"))
    )
    (net (code "138") (name "Net-(U$7-SWTEN)") (class "Default")
      (node (ref "U$7") (pin "36") (pinfunction "SWTEN_36") (pintype "bidirectional"))
      (node (ref "U$8") (pin "13") (pinfunction "S7_13") (pintype "bidirectional"))
    )
    (net (code "139") (name "Net-(U$7-V-)") (class "Default")
      (node (ref "U$7") (pin "31") (pinfunction "V-_31") (pintype "bidirectional"))
      (node (ref "U$8") (pin "18") (pinfunction "C4_18") (pintype "bidirectional"))
    )
    (net (code "140") (name "Net-(U$7-V-**)") (class "Default")
      (node (ref "U$7") (pin "30") (pinfunction "V-**_30") (pintype "bidirectional"))
      (node (ref "U$8") (pin "19") (pinfunction "S4_19") (pintype "bidirectional"))
    )
    (net (code "141") (name "Net-(U$7-VREF1)") (class "Default")
      (node (ref "U$7") (pin "35") (pinfunction "VREF1_35") (pintype "bidirectional"))
      (node (ref "U$8") (pin "14") (pinfunction "C6_14") (pintype "bidirectional"))
    )
    (net (code "142") (name "Net-(U$7-VREF2)") (class "Default")
      (node (ref "U$7") (pin "34") (pinfunction "VREF2_34") (pintype "bidirectional"))
      (node (ref "U$8") (pin "15") (pinfunction "S6_15") (pintype "bidirectional"))
    )
    (net (code "143") (name "Net-(U$7-VREG)") (class "Default")
      (node (ref "U$7") (pin "37") (pinfunction "VREG_37") (pintype "bidirectional"))
      (node (ref "U$8") (pin "12") (pinfunction "C7_12") (pintype "bidirectional"))
    )
    (net (code "144") (name "Net-(U$7-WDT)") (class "Default")
      (node (ref "U$7") (pin "39") (pinfunction "WDT_39") (pintype "bidirectional"))
      (node (ref "U$8") (pin "10") (pinfunction "C8_10") (pintype "bidirectional"))
    )
    (net (code "145") (name "Net-(U$8-A0)") (class "Default")
      (node (ref "U$8") (pin "45") (pinfunction "A0_45") (pintype "bidirectional"))
      (node (ref "U$9") (pin "4") (pinfunction "C11_4") (pintype "bidirectional"))
    )
    (net (code "146") (name "Net-(U$8-A1)") (class "Default")
      (node (ref "U$8") (pin "46") (pinfunction "A1_46") (pintype "bidirectional"))
      (node (ref "U$9") (pin "3") (pinfunction "S12_3") (pintype "bidirectional"))
    )
    (net (code "147") (name "Net-(U$8-A2)") (class "Default")
      (node (ref "U$8") (pin "47") (pinfunction "A2_47") (pintype "bidirectional"))
      (node (ref "U$9") (pin "2") (pinfunction "C12_2") (pintype "bidirectional"))
    )
    (net (code "148") (name "Net-(U$8-A3)") (class "Default")
      (node (ref "U$8") (pin "48") (pinfunction "A3_48") (pintype "bidirectional"))
      (node (ref "U$9") (pin "1") (pinfunction "V+_1") (pintype "bidirectional"))
    )
    (net (code "149") (name "Net-(U$8-C0)") (class "Default")
      (node (ref "U$8") (pin "26") (pinfunction "C0_26") (pintype "bidirectional"))
      (node (ref "U$9") (pin "23") (pinfunction "S2_23") (pintype "bidirectional"))
    )
    (net (code "150") (name "Net-(U$8-CSB(IMA))") (class "Default")
      (node (ref "U$8") (pin "41") (pinfunction "CSB(IMA)_41") (pintype "bidirectional"))
      (node (ref "U$9") (pin "8") (pinfunction "C9_8") (pintype "bidirectional"))
    )
    (net (code "151") (name "Net-(U$8-DRIVE)") (class "Default")
      (node (ref "U$8") (pin "38") (pinfunction "DRIVE_38") (pintype "bidirectional"))
      (node (ref "U$9") (pin "11") (pinfunction "S8_11") (pintype "bidirectional"))
    )
    (net (code "152") (name "Net-(U$8-GPI01)") (class "Default")
      (node (ref "U$8") (pin "27") (pinfunction "GPI01_27") (pintype "bidirectional"))
      (node (ref "U$9") (pin "22") (pinfunction "C2_22") (pintype "bidirectional"))
    )
    (net (code "153") (name "Net-(U$8-GPI02)") (class "Default")
      (node (ref "U$8") (pin "28") (pinfunction "GPI02_28") (pintype "bidirectional"))
      (node (ref "U$9") (pin "21") (pinfunction "S3_21") (pintype "bidirectional"))
    )
    (net (code "154") (name "Net-(U$8-GPI03)") (class "Default")
      (node (ref "U$8") (pin "29") (pinfunction "GPI03_29") (pintype "bidirectional"))
      (node (ref "U$9") (pin "20") (pinfunction "C3_20") (pintype "bidirectional"))
    )
    (net (code "155") (name "Net-(U$8-GPI04)") (class "Default")
      (node (ref "U$8") (pin "32") (pinfunction "GPI04_32") (pintype "bidirectional"))
      (node (ref "U$9") (pin "17") (pinfunction "S5_17") (pintype "bidirectional"))
    )
    (net (code "156") (name "Net-(U$8-GPI05)") (class "Default")
      (node (ref "U$8") (pin "33") (pinfunction "GPI05_33") (pintype "bidirectional"))
      (node (ref "U$9") (pin "16") (pinfunction "C5_16") (pintype "bidirectional"))
    )
    (net (code "157") (name "Net-(U$8-ISOMD)") (class "Default")
      (node (ref "U$8") (pin "40") (pinfunction "ISOMD_40") (pintype "bidirectional"))
      (node (ref "U$9") (pin "9") (pinfunction "S9_9") (pintype "bidirectional"))
    )
    (net (code "158") (name "Net-(U$8-S1)") (class "Default")
      (node (ref "U$8") (pin "25") (pinfunction "S1_25") (pintype "bidirectional"))
      (node (ref "U$9") (pin "24") (pinfunction "C1_24") (pintype "bidirectional"))
    )
    (net (code "159") (name "Net-(U$8-SCK(IPA))") (class "Default")
      (node (ref "U$8") (pin "42") (pinfunction "SCK(IPA)_42") (pintype "bidirectional"))
      (node (ref "U$9") (pin "7") (pinfunction "S10_7") (pintype "bidirectional"))
    )
    (net (code "160") (name "Net-(U$8-SDI(ICMP))") (class "Default")
      (node (ref "U$8") (pin "43") (pinfunction "SDI(ICMP)_43") (pintype "bidirectional"))
      (node (ref "U$9") (pin "6") (pinfunction "C10_6") (pintype "bidirectional"))
    )
    (net (code "161") (name "Net-(U$8-SDO(IBIAS))") (class "Default")
      (node (ref "U$8") (pin "44") (pinfunction "SDO(IBIAS)_44") (pintype "bidirectional"))
      (node (ref "U$9") (pin "5") (pinfunction "S11_5") (pintype "bidirectional"))
    )
    (net (code "162") (name "Net-(U$8-SWTEN)") (class "Default")
      (node (ref "U$8") (pin "36") (pinfunction "SWTEN_36") (pintype "bidirectional"))
      (node (ref "U$9") (pin "13") (pinfunction "S7_13") (pintype "bidirectional"))
    )
    (net (code "163") (name "Net-(U$8-V-)") (class "Default")
      (node (ref "U$8") (pin "31") (pinfunction "V-_31") (pintype "bidirectional"))
      (node (ref "U$9") (pin "18") (pinfunction "C4_18") (pintype "bidirectional"))
    )
    (net (code "164") (name "Net-(U$8-V-**)") (class "Default")
      (node (ref "U$8") (pin "30") (pinfunction "V-**_30") (pintype "bidirectional"))
      (node (ref "U$9") (pin "19") (pinfunction "S4_19") (pintype "bidirectional"))
    )
    (net (code "165") (name "Net-(U$8-VREF1)") (class "Default")
      (node (ref "U$8") (pin "35") (pinfunction "VREF1_35") (pintype "bidirectional"))
      (node (ref "U$9") (pin "14") (pinfunction "C6_14") (pintype "bidirectional"))
    )
    (net (code "166") (name "Net-(U$8-VREF2)") (class "Default")
      (node (ref "U$8") (pin "34") (pinfunction "VREF2_34") (pintype "bidirectional"))
      (node (ref "U$9") (pin "15") (pinfunction "S6_15") (pintype "bidirectional"))
    )
    (net (code "167") (name "Net-(U$8-VREG)") (class "Default")
      (node (ref "U$8") (pin "37") (pinfunction "VREG_37") (pintype "bidirectional"))
      (node (ref "U$9") (pin "12") (pinfunction "C7_12") (pintype "bidirectional"))
    )
    (net (code "168") (name "Net-(U$8-WDT)") (class "Default")
      (node (ref "U$8") (pin "39") (pinfunction "WDT_39") (pintype "bidirectional"))
      (node (ref "U$9") (pin "10") (pinfunction "C8_10") (pintype "bidirectional"))
    )
    (net (code "169") (name "Net-(U$10-A0)") (class "Default")
      (node (ref "U$10") (pin "45") (pinfunction "A0_45") (pintype "bidirectional"))
      (node (ref "U$11") (pin "4") (pinfunction "C11_4") (pintype "bidirectional"))
    )
    (net (code "170") (name "Net-(U$10-A1)") (class "Default")
      (node (ref "U$10") (pin "46") (pinfunction "A1_46") (pintype "bidirectional"))
      (node (ref "U$11") (pin "3") (pinfunction "S12_3") (pintype "bidirectional"))
    )
    (net (code "171") (name "Net-(U$10-A2)") (class "Default")
      (node (ref "U$10") (pin "47") (pinfunction "A2_47") (pintype "bidirectional"))
      (node (ref "U$11") (pin "2") (pinfunction "C12_2") (pintype "bidirectional"))
    )
    (net (code "172") (name "Net-(U$10-A3)") (class "Default")
      (node (ref "U$10") (pin "48") (pinfunction "A3_48") (pintype "bidirectional"))
      (node (ref "U$11") (pin "1") (pinfunction "V+_1") (pintype "bidirectional"))
    )
    (net (code "173") (name "Net-(U$10-C0)") (class "Default")
      (node (ref "U$10") (pin "26") (pinfunction "C0_26") (pintype "bidirectional"))
      (node (ref "U$11") (pin "23") (pinfunction "S2_23") (pintype "bidirectional"))
    )
    (net (code "174") (name "Net-(U$10-C1)") (class "Default")
      (node (ref "U$10") (pin "24") (pinfunction "C1_24") (pintype "bidirectional"))
      (node (ref "U$9") (pin "25") (pinfunction "S1_25") (pintype "bidirectional"))
    )
    (net (code "175") (name "Net-(U$10-C2)") (class "Default")
      (node (ref "U$10") (pin "22") (pinfunction "C2_22") (pintype "bidirectional"))
      (node (ref "U$9") (pin "27") (pinfunction "GPI01_27") (pintype "bidirectional"))
    )
    (net (code "176") (name "Net-(U$10-C3)") (class "Default")
      (node (ref "U$10") (pin "20") (pinfunction "C3_20") (pintype "bidirectional"))
      (node (ref "U$9") (pin "29") (pinfunction "GPI03_29") (pintype "bidirectional"))
    )
    (net (code "177") (name "Net-(U$10-C4)") (class "Default")
      (node (ref "U$10") (pin "18") (pinfunction "C4_18") (pintype "bidirectional"))
      (node (ref "U$9") (pin "31") (pinfunction "V-_31") (pintype "bidirectional"))
    )
    (net (code "178") (name "Net-(U$10-C5)") (class "Default")
      (node (ref "U$10") (pin "16") (pinfunction "C5_16") (pintype "bidirectional"))
      (node (ref "U$9") (pin "33") (pinfunction "GPI05_33") (pintype "bidirectional"))
    )
    (net (code "179") (name "Net-(U$10-C6)") (class "Default")
      (node (ref "U$10") (pin "14") (pinfunction "C6_14") (pintype "bidirectional"))
      (node (ref "U$9") (pin "35") (pinfunction "VREF1_35") (pintype "bidirectional"))
    )
    (net (code "180") (name "Net-(U$10-C7)") (class "Default")
      (node (ref "U$10") (pin "12") (pinfunction "C7_12") (pintype "bidirectional"))
      (node (ref "U$9") (pin "37") (pinfunction "VREG_37") (pintype "bidirectional"))
    )
    (net (code "181") (name "Net-(U$10-C8)") (class "Default")
      (node (ref "U$10") (pin "10") (pinfunction "C8_10") (pintype "bidirectional"))
      (node (ref "U$9") (pin "39") (pinfunction "WDT_39") (pintype "bidirectional"))
    )
    (net (code "182") (name "Net-(U$10-C9)") (class "Default")
      (node (ref "U$10") (pin "8") (pinfunction "C9_8") (pintype "bidirectional"))
      (node (ref "U$9") (pin "41") (pinfunction "CSB(IMA)_41") (pintype "bidirectional"))
    )
    (net (code "183") (name "Net-(U$10-C10)") (class "Default")
      (node (ref "U$10") (pin "6") (pinfunction "C10_6") (pintype "bidirectional"))
      (node (ref "U$9") (pin "43") (pinfunction "SDI(ICMP)_43") (pintype "bidirectional"))
    )
    (net (code "184") (name "Net-(U$10-C11)") (class "Default")
      (node (ref "U$10") (pin "4") (pinfunction "C11_4") (pintype "bidirectional"))
      (node (ref "U$9") (pin "45") (pinfunction "A0_45") (pintype "bidirectional"))
    )
    (net (code "185") (name "Net-(U$10-C12)") (class "Default")
      (node (ref "U$10") (pin "2") (pinfunction "C12_2") (pintype "bidirectional"))
      (node (ref "U$9") (pin "47") (pinfunction "A2_47") (pintype "bidirectional"))
    )
    (net (code "186") (name "Net-(U$10-CSB(IMA))") (class "Default")
      (node (ref "U$10") (pin "41") (pinfunction "CSB(IMA)_41") (pintype "bidirectional"))
      (node (ref "U$11") (pin "8") (pinfunction "C9_8") (pintype "bidirectional"))
    )
    (net (code "187") (name "Net-(U$10-DRIVE)") (class "Default")
      (node (ref "U$10") (pin "38") (pinfunction "DRIVE_38") (pintype "bidirectional"))
      (node (ref "U$11") (pin "11") (pinfunction "S8_11") (pintype "bidirectional"))
    )
    (net (code "188") (name "Net-(U$10-GPI01)") (class "Default")
      (node (ref "U$10") (pin "27") (pinfunction "GPI01_27") (pintype "bidirectional"))
      (node (ref "U$11") (pin "22") (pinfunction "C2_22") (pintype "bidirectional"))
    )
    (net (code "189") (name "Net-(U$10-GPI02)") (class "Default")
      (node (ref "U$10") (pin "28") (pinfunction "GPI02_28") (pintype "bidirectional"))
      (node (ref "U$11") (pin "21") (pinfunction "S3_21") (pintype "bidirectional"))
    )
    (net (code "190") (name "Net-(U$10-GPI03)") (class "Default")
      (node (ref "U$10") (pin "29") (pinfunction "GPI03_29") (pintype "bidirectional"))
      (node (ref "U$11") (pin "20") (pinfunction "C3_20") (pintype "bidirectional"))
    )
    (net (code "191") (name "Net-(U$10-GPI04)") (class "Default")
      (node (ref "U$10") (pin "32") (pinfunction "GPI04_32") (pintype "bidirectional"))
      (node (ref "U$11") (pin "17") (pinfunction "S5_17") (pintype "bidirectional"))
    )
    (net (code "192") (name "Net-(U$10-GPI05)") (class "Default")
      (node (ref "U$10") (pin "33") (pinfunction "GPI05_33") (pintype "bidirectional"))
      (node (ref "U$11") (pin "16") (pinfunction "C5_16") (pintype "bidirectional"))
    )
    (net (code "193") (name "Net-(U$10-ISOMD)") (class "Default")
      (node (ref "U$10") (pin "40") (pinfunction "ISOMD_40") (pintype "bidirectional"))
      (node (ref "U$11") (pin "9") (pinfunction "S9_9") (pintype "bidirectional"))
    )
    (net (code "194") (name "Net-(U$10-S1)") (class "Default")
      (node (ref "U$10") (pin "25") (pinfunction "S1_25") (pintype "bidirectional"))
      (node (ref "U$11") (pin "24") (pinfunction "C1_24") (pintype "bidirectional"))
    )
    (net (code "195") (name "Net-(U$10-S2)") (class "Default")
      (node (ref "U$10") (pin "23") (pinfunction "S2_23") (pintype "bidirectional"))
      (node (ref "U$9") (pin "26") (pinfunction "C0_26") (pintype "bidirectional"))
    )
    (net (code "196") (name "Net-(U$10-S3)") (class "Default")
      (node (ref "U$10") (pin "21") (pinfunction "S3_21") (pintype "bidirectional"))
      (node (ref "U$9") (pin "28") (pinfunction "GPI02_28") (pintype "bidirectional"))
    )
    (net (code "197") (name "Net-(U$10-S4)") (class "Default")
      (node (ref "U$10") (pin "19") (pinfunction "S4_19") (pintype "bidirectional"))
      (node (ref "U$9") (pin "30") (pinfunction "V-**_30") (pintype "bidirectional"))
    )
    (net (code "198") (name "Net-(U$10-S5)") (class "Default")
      (node (ref "U$10") (pin "17") (pinfunction "S5_17") (pintype "bidirectional"))
      (node (ref "U$9") (pin "32") (pinfunction "GPI04_32") (pintype "bidirectional"))
    )
    (net (code "199") (name "Net-(U$10-S6)") (class "Default")
      (node (ref "U$10") (pin "15") (pinfunction "S6_15") (pintype "bidirectional"))
      (node (ref "U$9") (pin "34") (pinfunction "VREF2_34") (pintype "bidirectional"))
    )
    (net (code "200") (name "Net-(U$10-S7)") (class "Default")
      (node (ref "U$10") (pin "13") (pinfunction "S7_13") (pintype "bidirectional"))
      (node (ref "U$9") (pin "36") (pinfunction "SWTEN_36") (pintype "bidirectional"))
    )
    (net (code "201") (name "Net-(U$10-S8)") (class "Default")
      (node (ref "U$10") (pin "11") (pinfunction "S8_11") (pintype "bidirectional"))
      (node (ref "U$9") (pin "38") (pinfunction "DRIVE_38") (pintype "bidirectional"))
    )
    (net (code "202") (name "Net-(U$10-S9)") (class "Default")
      (node (ref "U$10") (pin "9") (pinfunction "S9_9") (pintype "bidirectional"))
      (node (ref "U$9") (pin "40") (pinfunction "ISOMD_40") (pintype "bidirectional"))
    )
    (net (code "203") (name "Net-(U$10-S10)") (class "Default")
      (node (ref "U$10") (pin "7") (pinfunction "S10_7") (pintype "bidirectional"))
      (node (ref "U$9") (pin "42") (pinfunction "SCK(IPA)_42") (pintype "bidirectional"))
    )
    (net (code "204") (name "Net-(U$10-S11)") (class "Default")
      (node (ref "U$10") (pin "5") (pinfunction "S11_5") (pintype "bidirectional"))
      (node (ref "U$9") (pin "44") (pinfunction "SDO(IBIAS)_44") (pintype "bidirectional"))
    )
    (net (code "205") (name "Net-(U$10-S12)") (class "Default")
      (node (ref "U$10") (pin "3") (pinfunction "S12_3") (pintype "bidirectional"))
      (node (ref "U$9") (pin "46") (pinfunction "A1_46") (pintype "bidirectional"))
    )
    (net (code "206") (name "Net-(U$10-SCK(IPA))") (class "Default")
      (node (ref "U$10") (pin "42") (pinfunction "SCK(IPA)_42") (pintype "bidirectional"))
      (node (ref "U$11") (pin "7") (pinfunction "S10_7") (pintype "bidirectional"))
    )
    (net (code "207") (name "Net-(U$10-SDI(ICMP))") (class "Default")
      (node (ref "U$10") (pin "43") (pinfunction "SDI(ICMP)_43") (pintype "bidirectional"))
      (node (ref "U$11") (pin "6") (pinfunction "C10_6") (pintype "bidirectional"))
    )
    (net (code "208") (name "Net-(U$10-SDO(IBIAS))") (class "Default")
      (node (ref "U$10") (pin "44") (pinfunction "SDO(IBIAS)_44") (pintype "bidirectional"))
      (node (ref "U$11") (pin "5") (pinfunction "S11_5") (pintype "bidirectional"))
    )
    (net (code "209") (name "Net-(U$10-SWTEN)") (class "Default")
      (node (ref "U$10") (pin "36") (pinfunction "SWTEN_36") (pintype "bidirectional"))
      (node (ref "U$11") (pin "13") (pinfunction "S7_13") (pintype "bidirectional"))
    )
    (net (code "210") (name "Net-(U$10-V+)") (class "Default")
      (node (ref "U$10") (pin "1") (pinfunction "V+_1") (pintype "bidirectional"))
      (node (ref "U$9") (pin "48") (pinfunction "A3_48") (pintype "bidirectional"))
    )
    (net (code "211") (name "Net-(U$10-V-)") (class "Default")
      (node (ref "U$10") (pin "31") (pinfunction "V-_31") (pintype "bidirectional"))
      (node (ref "U$11") (pin "18") (pinfunction "C4_18") (pintype "bidirectional"))
    )
    (net (code "212") (name "Net-(U$10-V-**)") (class "Default")
      (node (ref "U$10") (pin "30") (pinfunction "V-**_30") (pintype "bidirectional"))
      (node (ref "U$11") (pin "19") (pinfunction "S4_19") (pintype "bidirectional"))
    )
    (net (code "213") (name "Net-(U$10-VREF1)") (class "Default")
      (node (ref "U$10") (pin "35") (pinfunction "VREF1_35") (pintype "bidirectional"))
      (node (ref "U$11") (pin "14") (pinfunction "C6_14") (pintype "bidirectional"))
    )
    (net (code "214") (name "Net-(U$10-VREF2)") (class "Default")
      (node (ref "U$10") (pin "34") (pinfunction "VREF2_34") (pintype "bidirectional"))
      (node (ref "U$11") (pin "15") (pinfunction "S6_15") (pintype "bidirectional"))
    )
    (net (code "215") (name "Net-(U$10-VREG)") (class "Default")
      (node (ref "U$10") (pin "37") (pinfunction "VREG_37") (pintype "bidirectional"))
      (node (ref "U$11") (pin "12") (pinfunction "C7_12") (pintype "bidirectional"))
    )
    (net (code "216") (name "Net-(U$10-WDT)") (class "Default")
      (node (ref "U$10") (pin "39") (pinfunction "WDT_39") (pintype "bidirectional"))
      (node (ref "U$11") (pin "10") (pinfunction "C8_10") (pintype "bidirectional"))
    )
    (net (code "217") (name "Net-(U$11-A0)") (class "Default")
      (node (ref "U$11") (pin "45") (pinfunction "A0_45") (pintype "bidirectional"))
      (node (ref "U$12") (pin "4") (pinfunction "C11_4") (pintype "bidirectional"))
    )
    (net (code "218") (name "Net-(U$11-A1)") (class "Default")
      (node (ref "U$11") (pin "46") (pinfunction "A1_46") (pintype "bidirectional"))
      (node (ref "U$12") (pin "3") (pinfunction "S12_3") (pintype "bidirectional"))
    )
    (net (code "219") (name "Net-(U$11-A2)") (class "Default")
      (node (ref "U$11") (pin "47") (pinfunction "A2_47") (pintype "bidirectional"))
      (node (ref "U$12") (pin "2") (pinfunction "C12_2") (pintype "bidirectional"))
    )
    (net (code "220") (name "Net-(U$11-A3)") (class "Default")
      (node (ref "U$11") (pin "48") (pinfunction "A3_48") (pintype "bidirectional"))
      (node (ref "U$12") (pin "1") (pinfunction "V+_1") (pintype "bidirectional"))
    )
    (net (code "221") (name "Net-(U$11-C0)") (class "Default")
      (node (ref "U$11") (pin "26") (pinfunction "C0_26") (pintype "bidirectional"))
      (node (ref "U$12") (pin "23") (pinfunction "S2_23") (pintype "bidirectional"))
    )
    (net (code "222") (name "Net-(U$11-CSB(IMA))") (class "Default")
      (node (ref "U$11") (pin "41") (pinfunction "CSB(IMA)_41") (pintype "bidirectional"))
      (node (ref "U$12") (pin "8") (pinfunction "C9_8") (pintype "bidirectional"))
    )
    (net (code "223") (name "Net-(U$11-DRIVE)") (class "Default")
      (node (ref "U$11") (pin "38") (pinfunction "DRIVE_38") (pintype "bidirectional"))
      (node (ref "U$12") (pin "11") (pinfunction "S8_11") (pintype "bidirectional"))
    )
    (net (code "224") (name "Net-(U$11-GPI01)") (class "Default")
      (node (ref "U$11") (pin "27") (pinfunction "GPI01_27") (pintype "bidirectional"))
      (node (ref "U$12") (pin "22") (pinfunction "C2_22") (pintype "bidirectional"))
    )
    (net (code "225") (name "Net-(U$11-GPI02)") (class "Default")
      (node (ref "U$11") (pin "28") (pinfunction "GPI02_28") (pintype "bidirectional"))
      (node (ref "U$12") (pin "21") (pinfunction "S3_21") (pintype "bidirectional"))
    )
    (net (code "226") (name "Net-(U$11-GPI03)") (class "Default")
      (node (ref "U$11") (pin "29") (pinfunction "GPI03_29") (pintype "bidirectional"))
      (node (ref "U$12") (pin "20") (pinfunction "C3_20") (pintype "bidirectional"))
    )
    (net (code "227") (name "Net-(U$11-GPI04)") (class "Default")
      (node (ref "U$11") (pin "32") (pinfunction "GPI04_32") (pintype "bidirectional"))
      (node (ref "U$12") (pin "17") (pinfunction "S5_17") (pintype "bidirectional"))
    )
    (net (code "228") (name "Net-(U$11-GPI05)") (class "Default")
      (node (ref "U$11") (pin "33") (pinfunction "GPI05_33") (pintype "bidirectional"))
      (node (ref "U$12") (pin "16") (pinfunction "C5_16") (pintype "bidirectional"))
    )
    (net (code "229") (name "Net-(U$11-ISOMD)") (class "Default")
      (node (ref "U$11") (pin "40") (pinfunction "ISOMD_40") (pintype "bidirectional"))
      (node (ref "U$12") (pin "9") (pinfunction "S9_9") (pintype "bidirectional"))
    )
    (net (code "230") (name "Net-(U$11-S1)") (class "Default")
      (node (ref "U$11") (pin "25") (pinfunction "S1_25") (pintype "bidirectional"))
      (node (ref "U$12") (pin "24") (pinfunction "C1_24") (pintype "bidirectional"))
    )
    (net (code "231") (name "Net-(U$11-SCK(IPA))") (class "Default")
      (node (ref "U$11") (pin "42") (pinfunction "SCK(IPA)_42") (pintype "bidirectional"))
      (node (ref "U$12") (pin "7") (pinfunction "S10_7") (pintype "bidirectional"))
    )
    (net (code "232") (name "Net-(U$11-SDI(ICMP))") (class "Default")
      (node (ref "U$11") (pin "43") (pinfunction "SDI(ICMP)_43") (pintype "bidirectional"))
      (node (ref "U$12") (pin "6") (pinfunction "C10_6") (pintype "bidirectional"))
    )
    (net (code "233") (name "Net-(U$11-SDO(IBIAS))") (class "Default")
      (node (ref "U$11") (pin "44") (pinfunction "SDO(IBIAS)_44") (pintype "bidirectional"))
      (node (ref "U$12") (pin "5") (pinfunction "S11_5") (pintype "bidirectional"))
    )
    (net (code "234") (name "Net-(U$11-SWTEN)") (class "Default")
      (node (ref "U$11") (pin "36") (pinfunction "SWTEN_36") (pintype "bidirectional"))
      (node (ref "U$12") (pin "13") (pinfunction "S7_13") (pintype "bidirectional"))
    )
    (net (code "235") (name "Net-(U$11-V-)") (class "Default")
      (node (ref "U$11") (pin "31") (pinfunction "V-_31") (pintype "bidirectional"))
      (node (ref "U$12") (pin "18") (pinfunction "C4_18") (pintype "bidirectional"))
    )
    (net (code "236") (name "Net-(U$11-V-**)") (class "Default")
      (node (ref "U$11") (pin "30") (pinfunction "V-**_30") (pintype "bidirectional"))
      (node (ref "U$12") (pin "19") (pinfunction "S4_19") (pintype "bidirectional"))
    )
    (net (code "237") (name "Net-(U$11-VREF1)") (class "Default")
      (node (ref "U$11") (pin "35") (pinfunction "VREF1_35") (pintype "bidirectional"))
      (node (ref "U$12") (pin "14") (pinfunction "C6_14") (pintype "bidirectional"))
    )
    (net (code "238") (name "Net-(U$11-VREF2)") (class "Default")
      (node (ref "U$11") (pin "34") (pinfunction "VREF2_34") (pintype "bidirectional"))
      (node (ref "U$12") (pin "15") (pinfunction "S6_15") (pintype "bidirectional"))
    )
    (net (code "239") (name "Net-(U$11-VREG)") (class "Default")
      (node (ref "U$11") (pin "37") (pinfunction "VREG_37") (pintype "bidirectional"))
      (node (ref "U$12") (pin "12") (pinfunction "C7_12") (pintype "bidirectional"))
    )
    (net (code "240") (name "Net-(U$11-WDT)") (class "Default")
      (node (ref "U$11") (pin "39") (pinfunction "WDT_39") (pintype "bidirectional"))
      (node (ref "U$12") (pin "10") (pinfunction "C8_10") (pintype "bidirectional"))
    )
    (net (code "241") (name "Net-(U$13-A0)") (class "Default")
      (node (ref "U$13") (pin "45") (pinfunction "A0_45") (pintype "bidirectional"))
      (node (ref "U$14") (pin "4") (pinfunction "C11_4") (pintype "bidirectional"))
    )
    (net (code "242") (name "Net-(U$13-A1)") (class "Default")
      (node (ref "U$13") (pin "46") (pinfunction "A1_46") (pintype "bidirectional"))
      (node (ref "U$14") (pin "3") (pinfunction "S12_3") (pintype "bidirectional"))
    )
    (net (code "243") (name "Net-(U$13-A2)") (class "Default")
      (node (ref "U$13") (pin "47") (pinfunction "A2_47") (pintype "bidirectional"))
      (node (ref "U$14") (pin "2") (pinfunction "C12_2") (pintype "bidirectional"))
    )
    (net (code "244") (name "Net-(U$13-A3)") (class "Default")
      (node (ref "U$13") (pin "48") (pinfunction "A3_48") (pintype "bidirectional"))
      (node (ref "U$14") (pin "1") (pinfunction "V+_1") (pintype "bidirectional"))
    )
    (net (code "245") (name "Net-(U$13-C0)") (class "Default")
      (node (ref "U$13") (pin "26") (pinfunction "C0_26") (pintype "bidirectional"))
      (node (ref "U$14") (pin "23") (pinfunction "S2_23") (pintype "bidirectional"))
    )
    (net (code "246") (name "Net-(U$13-CSB(IMA))") (class "Default")
      (node (ref "U$13") (pin "41") (pinfunction "CSB(IMA)_41") (pintype "bidirectional"))
      (node (ref "U$14") (pin "8") (pinfunction "C9_8") (pintype "bidirectional"))
    )
    (net (code "247") (name "Net-(U$13-DRIVE)") (class "Default")
      (node (ref "U$13") (pin "38") (pinfunction "DRIVE_38") (pintype "bidirectional"))
      (node (ref "U$14") (pin "11") (pinfunction "S8_11") (pintype "bidirectional"))
    )
    (net (code "248") (name "Net-(U$13-GPI01)") (class "Default")
      (node (ref "U$13") (pin "27") (pinfunction "GPI01_27") (pintype "bidirectional"))
      (node (ref "U$14") (pin "22") (pinfunction "C2_22") (pintype "bidirectional"))
    )
    (net (code "249") (name "Net-(U$13-GPI02)") (class "Default")
      (node (ref "U$13") (pin "28") (pinfunction "GPI02_28") (pintype "bidirectional"))
      (node (ref "U$14") (pin "21") (pinfunction "S3_21") (pintype "bidirectional"))
    )
    (net (code "250") (name "Net-(U$13-GPI03)") (class "Default")
      (node (ref "U$13") (pin "29") (pinfunction "GPI03_29") (pintype "bidirectional"))
      (node (ref "U$14") (pin "20") (pinfunction "C3_20") (pintype "bidirectional"))
    )
    (net (code "251") (name "Net-(U$13-GPI04)") (class "Default")
      (node (ref "U$13") (pin "32") (pinfunction "GPI04_32") (pintype "bidirectional"))
      (node (ref "U$14") (pin "17") (pinfunction "S5_17") (pintype "bidirectional"))
    )
    (net (code "252") (name "Net-(U$13-GPI05)") (class "Default")
      (node (ref "U$13") (pin "33") (pinfunction "GPI05_33") (pintype "bidirectional"))
      (node (ref "U$14") (pin "16") (pinfunction "C5_16") (pintype "bidirectional"))
    )
    (net (code "253") (name "Net-(U$13-ISOMD)") (class "Default")
      (node (ref "U$13") (pin "40") (pinfunction "ISOMD_40") (pintype "bidirectional"))
      (node (ref "U$14") (pin "9") (pinfunction "S9_9") (pintype "bidirectional"))
    )
    (net (code "254") (name "Net-(U$13-S1)") (class "Default")
      (node (ref "U$13") (pin "25") (pinfunction "S1_25") (pintype "bidirectional"))
      (node (ref "U$14") (pin "24") (pinfunction "C1_24") (pintype "bidirectional"))
    )
    (net (code "255") (name "Net-(U$13-SCK(IPA))") (class "Default")
      (node (ref "U$13") (pin "42") (pinfunction "SCK(IPA)_42") (pintype "bidirectional"))
      (node (ref "U$14") (pin "7") (pinfunction "S10_7") (pintype "bidirectional"))
    )
    (net (code "256") (name "Net-(U$13-SDI(ICMP))") (class "Default")
      (node (ref "U$13") (pin "43") (pinfunction "SDI(ICMP)_43") (pintype "bidirectional"))
      (node (ref "U$14") (pin "6") (pinfunction "C10_6") (pintype "bidirectional"))
    )
    (net (code "257") (name "Net-(U$13-SDO(IBIAS))") (class "Default")
      (node (ref "U$13") (pin "44") (pinfunction "SDO(IBIAS)_44") (pintype "bidirectional"))
      (node (ref "U$14") (pin "5") (pinfunction "S11_5") (pintype "bidirectional"))
    )
    (net (code "258") (name "Net-(U$13-SWTEN)") (class "Default")
      (node (ref "U$13") (pin "36") (pinfunction "SWTEN_36") (pintype "bidirectional"))
      (node (ref "U$14") (pin "13") (pinfunction "S7_13") (pintype "bidirectional"))
    )
    (net (code "259") (name "Net-(U$13-V-)") (class "Default")
      (node (ref "U$13") (pin "31") (pinfunction "V-_31") (pintype "bidirectional"))
      (node (ref "U$14") (pin "18") (pinfunction "C4_18") (pintype "bidirectional"))
    )
    (net (code "260") (name "Net-(U$13-V-**)") (class "Default")
      (node (ref "U$13") (pin "30") (pinfunction "V-**_30") (pintype "bidirectional"))
      (node (ref "U$14") (pin "19") (pinfunction "S4_19") (pintype "bidirectional"))
    )
    (net (code "261") (name "Net-(U$13-VREF1)") (class "Default")
      (node (ref "U$13") (pin "35") (pinfunction "VREF1_35") (pintype "bidirectional"))
      (node (ref "U$14") (pin "14") (pinfunction "C6_14") (pintype "bidirectional"))
    )
    (net (code "262") (name "Net-(U$13-VREF2)") (class "Default")
      (node (ref "U$13") (pin "34") (pinfunction "VREF2_34") (pintype "bidirectional"))
      (node (ref "U$14") (pin "15") (pinfunction "S6_15") (pintype "bidirectional"))
    )
    (net (code "263") (name "Net-(U$13-VREG)") (class "Default")
      (node (ref "U$13") (pin "37") (pinfunction "VREG_37") (pintype "bidirectional"))
      (node (ref "U$14") (pin "12") (pinfunction "C7_12") (pintype "bidirectional"))
    )
    (net (code "264") (name "Net-(U$13-WDT)") (class "Default")
      (node (ref "U$13") (pin "39") (pinfunction "WDT_39") (pintype "bidirectional"))
      (node (ref "U$14") (pin "10") (pinfunction "C8_10") (pintype "bidirectional"))
    )
    (net (code "265") (name "Net-(U$14-A0)") (class "Default")
      (node (ref "U$14") (pin "45") (pinfunction "A0_45") (pintype "bidirectional"))
      (node (ref "U$15") (pin "4") (pinfunction "C11_4") (pintype "bidirectional"))
    )
    (net (code "266") (name "Net-(U$14-A1)") (class "Default")
      (node (ref "U$14") (pin "46") (pinfunction "A1_46") (pintype "bidirectional"))
      (node (ref "U$15") (pin "3") (pinfunction "S12_3") (pintype "bidirectional"))
    )
    (net (code "267") (name "Net-(U$14-A2)") (class "Default")
      (node (ref "U$14") (pin "47") (pinfunction "A2_47") (pintype "bidirectional"))
      (node (ref "U$15") (pin "2") (pinfunction "C12_2") (pintype "bidirectional"))
    )
    (net (code "268") (name "Net-(U$14-A3)") (class "Default")
      (node (ref "U$14") (pin "48") (pinfunction "A3_48") (pintype "bidirectional"))
      (node (ref "U$15") (pin "1") (pinfunction "V+_1") (pintype "bidirectional"))
    )
    (net (code "269") (name "Net-(U$14-C0)") (class "Default")
      (node (ref "U$14") (pin "26") (pinfunction "C0_26") (pintype "bidirectional"))
      (node (ref "U$15") (pin "23") (pinfunction "S2_23") (pintype "bidirectional"))
    )
    (net (code "270") (name "Net-(U$14-CSB(IMA))") (class "Default")
      (node (ref "U$14") (pin "41") (pinfunction "CSB(IMA)_41") (pintype "bidirectional"))
      (node (ref "U$15") (pin "8") (pinfunction "C9_8") (pintype "bidirectional"))
    )
    (net (code "271") (name "Net-(U$14-DRIVE)") (class "Default")
      (node (ref "U$14") (pin "38") (pinfunction "DRIVE_38") (pintype "bidirectional"))
      (node (ref "U$15") (pin "11") (pinfunction "S8_11") (pintype "bidirectional"))
    )
    (net (code "272") (name "Net-(U$14-GPI01)") (class "Default")
      (node (ref "U$14") (pin "27") (pinfunction "GPI01_27") (pintype "bidirectional"))
      (node (ref "U$15") (pin "22") (pinfunction "C2_22") (pintype "bidirectional"))
    )
    (net (code "273") (name "Net-(U$14-GPI02)") (class "Default")
      (node (ref "U$14") (pin "28") (pinfunction "GPI02_28") (pintype "bidirectional"))
      (node (ref "U$15") (pin "21") (pinfunction "S3_21") (pintype "bidirectional"))
    )
    (net (code "274") (name "Net-(U$14-GPI03)") (class "Default")
      (node (ref "U$14") (pin "29") (pinfunction "GPI03_29") (pintype "bidirectional"))
      (node (ref "U$15") (pin "20") (pinfunction "C3_20") (pintype "bidirectional"))
    )
    (net (code "275") (name "Net-(U$14-GPI04)") (class "Default")
      (node (ref "U$14") (pin "32") (pinfunction "GPI04_32") (pintype "bidirectional"))
      (node (ref "U$15") (pin "17") (pinfunction "S5_17") (pintype "bidirectional"))
    )
    (net (code "276") (name "Net-(U$14-GPI05)") (class "Default")
      (node (ref "U$14") (pin "33") (pinfunction "GPI05_33") (pintype "bidirectional"))
      (node (ref "U$15") (pin "16") (pinfunction "C5_16") (pintype "bidirectional"))
    )
    (net (code "277") (name "Net-(U$14-ISOMD)") (class "Default")
      (node (ref "U$14") (pin "40") (pinfunction "ISOMD_40") (pintype "bidirectional"))
      (node (ref "U$15") (pin "9") (pinfunction "S9_9") (pintype "bidirectional"))
    )
    (net (code "278") (name "Net-(U$14-S1)") (class "Default")
      (node (ref "U$14") (pin "25") (pinfunction "S1_25") (pintype "bidirectional"))
      (node (ref "U$15") (pin "24") (pinfunction "C1_24") (pintype "bidirectional"))
    )
    (net (code "279") (name "Net-(U$14-SCK(IPA))") (class "Default")
      (node (ref "U$14") (pin "42") (pinfunction "SCK(IPA)_42") (pintype "bidirectional"))
      (node (ref "U$15") (pin "7") (pinfunction "S10_7") (pintype "bidirectional"))
    )
    (net (code "280") (name "Net-(U$14-SDI(ICMP))") (class "Default")
      (node (ref "U$14") (pin "43") (pinfunction "SDI(ICMP)_43") (pintype "bidirectional"))
      (node (ref "U$15") (pin "6") (pinfunction "C10_6") (pintype "bidirectional"))
    )
    (net (code "281") (name "Net-(U$14-SDO(IBIAS))") (class "Default")
      (node (ref "U$14") (pin "44") (pinfunction "SDO(IBIAS)_44") (pintype "bidirectional"))
      (node (ref "U$15") (pin "5") (pinfunction "S11_5") (pintype "bidirectional"))
    )
    (net (code "282") (name "Net-(U$14-SWTEN)") (class "Default")
      (node (ref "U$14") (pin "36") (pinfunction "SWTEN_36") (pintype "bidirectional"))
      (node (ref "U$15") (pin "13") (pinfunction "S7_13") (pintype "bidirectional"))
    )
    (net (code "283") (name "Net-(U$14-V-)") (class "Default")
      (node (ref "U$14") (pin "31") (pinfunction "V-_31") (pintype "bidirectional"))
      (node (ref "U$15") (pin "18") (pinfunction "C4_18") (pintype "bidirectional"))
    )
    (net (code "284") (name "Net-(U$14-V-**)") (class "Default")
      (node (ref "U$14") (pin "30") (pinfunction "V-**_30") (pintype "bidirectional"))
      (node (ref "U$15") (pin "19") (pinfunction "S4_19") (pintype "bidirectional"))
    )
    (net (code "285") (name "Net-(U$14-VREF1)") (class "Default")
      (node (ref "U$14") (pin "35") (pinfunction "VREF1_35") (pintype "bidirectional"))
      (node (ref "U$15") (pin "14") (pinfunction "C6_14") (pintype "bidirectional"))
    )
    (net (code "286") (name "Net-(U$14-VREF2)") (class "Default")
      (node (ref "U$14") (pin "34") (pinfunction "VREF2_34") (pintype "bidirectional"))
      (node (ref "U$15") (pin "15") (pinfunction "S6_15") (pintype "bidirectional"))
    )
    (net (code "287") (name "Net-(U$14-VREG)") (class "Default")
      (node (ref "U$14") (pin "37") (pinfunction "VREG_37") (pintype "bidirectional"))
      (node (ref "U$15") (pin "12") (pinfunction "C7_12") (pintype "bidirectional"))
    )
    (net (code "288") (name "Net-(U$14-WDT)") (class "Default")
      (node (ref "U$14") (pin "39") (pinfunction "WDT_39") (pintype "bidirectional"))
      (node (ref "U$15") (pin "10") (pinfunction "C8_10") (pintype "bidirectional"))
    )
    (net (code "289") (name "Net-(U$15-A0)") (class "Default")
      (node (ref "U$15") (pin "45") (pinfunction "A0_45") (pintype "bidirectional"))
      (node (ref "U$16") (pin "4") (pinfunction "C11_4") (pintype "bidirectional"))
    )
    (net (code "290") (name "Net-(U$15-A1)") (class "Default")
      (node (ref "U$15") (pin "46") (pinfunction "A1_46") (pintype "bidirectional"))
      (node (ref "U$16") (pin "3") (pinfunction "S12_3") (pintype "bidirectional"))
    )
    (net (code "291") (name "Net-(U$15-A2)") (class "Default")
      (node (ref "U$15") (pin "47") (pinfunction "A2_47") (pintype "bidirectional"))
      (node (ref "U$16") (pin "2") (pinfunction "C12_2") (pintype "bidirectional"))
    )
    (net (code "292") (name "Net-(U$15-A3)") (class "Default")
      (node (ref "U$15") (pin "48") (pinfunction "A3_48") (pintype "bidirectional"))
      (node (ref "U$16") (pin "1") (pinfunction "V+_1") (pintype "bidirectional"))
    )
    (net (code "293") (name "Net-(U$15-C0)") (class "Default")
      (node (ref "U$15") (pin "26") (pinfunction "C0_26") (pintype "bidirectional"))
      (node (ref "U$16") (pin "23") (pinfunction "S2_23") (pintype "bidirectional"))
    )
    (net (code "294") (name "Net-(U$15-CSB(IMA))") (class "Default")
      (node (ref "U$15") (pin "41") (pinfunction "CSB(IMA)_41") (pintype "bidirectional"))
      (node (ref "U$16") (pin "8") (pinfunction "C9_8") (pintype "bidirectional"))
    )
    (net (code "295") (name "Net-(U$15-DRIVE)") (class "Default")
      (node (ref "U$15") (pin "38") (pinfunction "DRIVE_38") (pintype "bidirectional"))
      (node (ref "U$16") (pin "11") (pinfunction "S8_11") (pintype "bidirectional"))
    )
    (net (code "296") (name "Net-(U$15-GPI01)") (class "Default")
      (node (ref "U$15") (pin "27") (pinfunction "GPI01_27") (pintype "bidirectional"))
      (node (ref "U$16") (pin "22") (pinfunction "C2_22") (pintype "bidirectional"))
    )
    (net (code "297") (name "Net-(U$15-GPI02)") (class "Default")
      (node (ref "U$15") (pin "28") (pinfunction "GPI02_28") (pintype "bidirectional"))
      (node (ref "U$16") (pin "21") (pinfunction "S3_21") (pintype "bidirectional"))
    )
    (net (code "298") (name "Net-(U$15-GPI03)") (class "Default")
      (node (ref "U$15") (pin "29") (pinfunction "GPI03_29") (pintype "bidirectional"))
      (node (ref "U$16") (pin "20") (pinfunction "C3_20") (pintype "bidirectional"))
    )
    (net (code "299") (name "Net-(U$15-GPI04)") (class "Default")
      (node (ref "U$15") (pin "32") (pinfunction "GPI04_32") (pintype "bidirectional"))
      (node (ref "U$16") (pin "17") (pinfunction "S5_17") (pintype "bidirectional"))
    )
    (net (code "300") (name "Net-(U$15-GPI05)") (class "Default")
      (node (ref "U$15") (pin "33") (pinfunction "GPI05_33") (pintype "bidirectional"))
      (node (ref "U$16") (pin "16") (pinfunction "C5_16") (pintype "bidirectional"))
    )
    (net (code "301") (name "Net-(U$15-ISOMD)") (class "Default")
      (node (ref "U$15") (pin "40") (pinfunction "ISOMD_40") (pintype "bidirectional"))
      (node (ref "U$16") (pin "9") (pinfunction "S9_9") (pintype "bidirectional"))
    )
    (net (code "302") (name "Net-(U$15-S1)") (class "Default")
      (node (ref "U$15") (pin "25") (pinfunction "S1_25") (pintype "bidirectional"))
      (node (ref "U$16") (pin "24") (pinfunction "C1_24") (pintype "bidirectional"))
    )
    (net (code "303") (name "Net-(U$15-SCK(IPA))") (class "Default")
      (node (ref "U$15") (pin "42") (pinfunction "SCK(IPA)_42") (pintype "bidirectional"))
      (node (ref "U$16") (pin "7") (pinfunction "S10_7") (pintype "bidirectional"))
    )
    (net (code "304") (name "Net-(U$15-SDI(ICMP))") (class "Default")
      (node (ref "U$15") (pin "43") (pinfunction "SDI(ICMP)_43") (pintype "bidirectional"))
      (node (ref "U$16") (pin "6") (pinfunction "C10_6") (pintype "bidirectional"))
    )
    (net (code "305") (name "Net-(U$15-SDO(IBIAS))") (class "Default")
      (node (ref "U$15") (pin "44") (pinfunction "SDO(IBIAS)_44") (pintype "bidirectional"))
      (node (ref "U$16") (pin "5") (pinfunction "S11_5") (pintype "bidirectional"))
    )
    (net (code "306") (name "Net-(U$15-SWTEN)") (class "Default")
      (node (ref "U$15") (pin "36") (pinfunction "SWTEN_36") (pintype "bidirectional"))
      (node (ref "U$16") (pin "13") (pinfunction "S7_13") (pintype "bidirectional"))
    )
    (net (code "307") (name "Net-(U$15-V-)") (class "Default")
      (node (ref "U$15") (pin "31") (pinfunction "V-_31") (pintype "bidirectional"))
      (node (ref "U$16") (pin "18") (pinfunction "C4_18") (pintype "bidirectional"))
    )
    (net (code "308") (name "Net-(U$15-V-**)") (class "Default")
      (node (ref "U$15") (pin "30") (pinfunction "V-**_30") (pintype "bidirectional"))
      (node (ref "U$16") (pin "19") (pinfunction "S4_19") (pintype "bidirectional"))
    )
    (net (code "309") (name "Net-(U$15-VREF1)") (class "Default")
      (node (ref "U$15") (pin "35") (pinfunction "VREF1_35") (pintype "bidirectional"))
      (node (ref "U$16") (pin "14") (pinfunction "C6_14") (pintype "bidirectional"))
    )
    (net (code "310") (name "Net-(U$15-VREF2)") (class "Default")
      (node (ref "U$15") (pin "34") (pinfunction "VREF2_34") (pintype "bidirectional"))
      (node (ref "U$16") (pin "15") (pinfunction "S6_15") (pintype "bidirectional"))
    )
    (net (code "311") (name "Net-(U$15-VREG)") (class "Default")
      (node (ref "U$15") (pin "37") (pinfunction "VREG_37") (pintype "bidirectional"))
      (node (ref "U$16") (pin "12") (pinfunction "C7_12") (pintype "bidirectional"))
    )
    (net (code "312") (name "Net-(U$15-WDT)") (class "Default")
      (node (ref "U$15") (pin "39") (pinfunction "WDT_39") (pintype "bidirectional"))
      (node (ref "U$16") (pin "10") (pinfunction "C8_10") (pintype "bidirectional"))
    )
    (net (code "313") (name "Net-(U$16-A0)") (class "Default")
      (node (ref "U$16") (pin "45") (pinfunction "A0_45") (pintype "bidirectional"))
      (node (ref "U$17") (pin "4") (pinfunction "C11_4") (pintype "bidirectional"))
    )
    (net (code "314") (name "Net-(U$16-A1)") (class "Default")
      (node (ref "U$16") (pin "46") (pinfunction "A1_46") (pintype "bidirectional"))
      (node (ref "U$17") (pin "3") (pinfunction "S12_3") (pintype "bidirectional"))
    )
    (net (code "315") (name "Net-(U$16-A2)") (class "Default")
      (node (ref "U$16") (pin "47") (pinfunction "A2_47") (pintype "bidirectional"))
      (node (ref "U$17") (pin "2") (pinfunction "C12_2") (pintype "bidirectional"))
    )
    (net (code "316") (name "Net-(U$16-A3)") (class "Default")
      (node (ref "U$16") (pin "48") (pinfunction "A3_48") (pintype "bidirectional"))
      (node (ref "U$17") (pin "1") (pinfunction "V+_1") (pintype "bidirectional"))
    )
    (net (code "317") (name "Net-(U$16-C0)") (class "Default")
      (node (ref "U$16") (pin "26") (pinfunction "C0_26") (pintype "bidirectional"))
      (node (ref "U$17") (pin "23") (pinfunction "S2_23") (pintype "bidirectional"))
    )
    (net (code "318") (name "Net-(U$16-CSB(IMA))") (class "Default")
      (node (ref "U$16") (pin "41") (pinfunction "CSB(IMA)_41") (pintype "bidirectional"))
      (node (ref "U$17") (pin "8") (pinfunction "C9_8") (pintype "bidirectional"))
    )
    (net (code "319") (name "Net-(U$16-DRIVE)") (class "Default")
      (node (ref "U$16") (pin "38") (pinfunction "DRIVE_38") (pintype "bidirectional"))
      (node (ref "U$17") (pin "11") (pinfunction "S8_11") (pintype "bidirectional"))
    )
    (net (code "320") (name "Net-(U$16-GPI01)") (class "Default")
      (node (ref "U$16") (pin "27") (pinfunction "GPI01_27") (pintype "bidirectional"))
      (node (ref "U$17") (pin "22") (pinfunction "C2_22") (pintype "bidirectional"))
    )
    (net (code "321") (name "Net-(U$16-GPI02)") (class "Default")
      (node (ref "U$16") (pin "28") (pinfunction "GPI02_28") (pintype "bidirectional"))
      (node (ref "U$17") (pin "21") (pinfunction "S3_21") (pintype "bidirectional"))
    )
    (net (code "322") (name "Net-(U$16-GPI03)") (class "Default")
      (node (ref "U$16") (pin "29") (pinfunction "GPI03_29") (pintype "bidirectional"))
      (node (ref "U$17") (pin "20") (pinfunction "C3_20") (pintype "bidirectional"))
    )
    (net (code "323") (name "Net-(U$16-GPI04)") (class "Default")
      (node (ref "U$16") (pin "32") (pinfunction "GPI04_32") (pintype "bidirectional"))
      (node (ref "U$17") (pin "17") (pinfunction "S5_17") (pintype "bidirectional"))
    )
    (net (code "324") (name "Net-(U$16-GPI05)") (class "Default")
      (node (ref "U$16") (pin "33") (pinfunction "GPI05_33") (pintype "bidirectional"))
      (node (ref "U$17") (pin "16") (pinfunction "C5_16") (pintype "bidirectional"))
    )
    (net (code "325") (name "Net-(U$16-ISOMD)") (class "Default")
      (node (ref "U$16") (pin "40") (pinfunction "ISOMD_40") (pintype "bidirectional"))
      (node (ref "U$17") (pin "9") (pinfunction "S9_9") (pintype "bidirectional"))
    )
    (net (code "326") (name "Net-(U$16-S1)") (class "Default")
      (node (ref "U$16") (pin "25") (pinfunction "S1_25") (pintype "bidirectional"))
      (node (ref "U$17") (pin "24") (pinfunction "C1_24") (pintype "bidirectional"))
    )
    (net (code "327") (name "Net-(U$16-SCK(IPA))") (class "Default")
      (node (ref "U$16") (pin "42") (pinfunction "SCK(IPA)_42") (pintype "bidirectional"))
      (node (ref "U$17") (pin "7") (pinfunction "S10_7") (pintype "bidirectional"))
    )
    (net (code "328") (name "Net-(U$16-SDI(ICMP))") (class "Default")
      (node (ref "U$16") (pin "43") (pinfunction "SDI(ICMP)_43") (pintype "bidirectional"))
      (node (ref "U$17") (pin "6") (pinfunction "C10_6") (pintype "bidirectional"))
    )
    (net (code "329") (name "Net-(U$16-SDO(IBIAS))") (class "Default")
      (node (ref "U$16") (pin "44") (pinfunction "SDO(IBIAS)_44") (pintype "bidirectional"))
      (node (ref "U$17") (pin "5") (pinfunction "S11_5") (pintype "bidirectional"))
    )
    (net (code "330") (name "Net-(U$16-SWTEN)") (class "Default")
      (node (ref "U$16") (pin "36") (pinfunction "SWTEN_36") (pintype "bidirectional"))
      (node (ref "U$17") (pin "13") (pinfunction "S7_13") (pintype "bidirectional"))
    )
    (net (code "331") (name "Net-(U$16-V-)") (class "Default")
      (node (ref "U$16") (pin "31") (pinfunction "V-_31") (pintype "bidirectional"))
      (node (ref "U$17") (pin "18") (pinfunction "C4_18") (pintype "bidirectional"))
    )
    (net (code "332") (name "Net-(U$16-V-**)") (class "Default")
      (node (ref "U$16") (pin "30") (pinfunction "V-**_30") (pintype "bidirectional"))
      (node (ref "U$17") (pin "19") (pinfunction "S4_19") (pintype "bidirectional"))
    )
    (net (code "333") (name "Net-(U$16-VREF1)") (class "Default")
      (node (ref "U$16") (pin "35") (pinfunction "VREF1_35") (pintype "bidirectional"))
      (node (ref "U$17") (pin "14") (pinfunction "C6_14") (pintype "bidirectional"))
    )
    (net (code "334") (name "Net-(U$16-VREF2)") (class "Default")
      (node (ref "U$16") (pin "34") (pinfunction "VREF2_34") (pintype "bidirectional"))
      (node (ref "U$17") (pin "15") (pinfunction "S6_15") (pintype "bidirectional"))
    )
    (net (code "335") (name "Net-(U$16-VREG)") (class "Default")
      (node (ref "U$16") (pin "37") (pinfunction "VREG_37") (pintype "bidirectional"))
      (node (ref "U$17") (pin "12") (pinfunction "C7_12") (pintype "bidirectional"))
    )
    (net (code "336") (name "Net-(U$16-WDT)") (class "Default")
      (node (ref "U$16") (pin "39") (pinfunction "WDT_39") (pintype "bidirectional"))
      (node (ref "U$17") (pin "10") (pinfunction "C8_10") (pintype "bidirectional"))
    )
    (net (code "337") (name "Net-(U$17-A0)") (class "Default")
      (node (ref "U$17") (pin "45") (pinfunction "A0_45") (pintype "bidirectional"))
      (node (ref "U$18") (pin "4") (pinfunction "C11_4") (pintype "bidirectional"))
    )
    (net (code "338") (name "Net-(U$17-A1)") (class "Default")
      (node (ref "U$17") (pin "46") (pinfunction "A1_46") (pintype "bidirectional"))
      (node (ref "U$18") (pin "3") (pinfunction "S12_3") (pintype "bidirectional"))
    )
    (net (code "339") (name "Net-(U$17-A2)") (class "Default")
      (node (ref "U$17") (pin "47") (pinfunction "A2_47") (pintype "bidirectional"))
      (node (ref "U$18") (pin "2") (pinfunction "C12_2") (pintype "bidirectional"))
    )
    (net (code "340") (name "Net-(U$17-A3)") (class "Default")
      (node (ref "U$17") (pin "48") (pinfunction "A3_48") (pintype "bidirectional"))
      (node (ref "U$18") (pin "1") (pinfunction "V+_1") (pintype "bidirectional"))
    )
    (net (code "341") (name "Net-(U$17-C0)") (class "Default")
      (node (ref "U$17") (pin "26") (pinfunction "C0_26") (pintype "bidirectional"))
      (node (ref "U$18") (pin "23") (pinfunction "S2_23") (pintype "bidirectional"))
    )
    (net (code "342") (name "Net-(U$17-CSB(IMA))") (class "Default")
      (node (ref "U$17") (pin "41") (pinfunction "CSB(IMA)_41") (pintype "bidirectional"))
      (node (ref "U$18") (pin "8") (pinfunction "C9_8") (pintype "bidirectional"))
    )
    (net (code "343") (name "Net-(U$17-DRIVE)") (class "Default")
      (node (ref "U$17") (pin "38") (pinfunction "DRIVE_38") (pintype "bidirectional"))
      (node (ref "U$18") (pin "11") (pinfunction "S8_11") (pintype "bidirectional"))
    )
    (net (code "344") (name "Net-(U$17-GPI01)") (class "Default")
      (node (ref "U$17") (pin "27") (pinfunction "GPI01_27") (pintype "bidirectional"))
      (node (ref "U$18") (pin "22") (pinfunction "C2_22") (pintype "bidirectional"))
    )
    (net (code "345") (name "Net-(U$17-GPI02)") (class "Default")
      (node (ref "U$17") (pin "28") (pinfunction "GPI02_28") (pintype "bidirectional"))
      (node (ref "U$18") (pin "21") (pinfunction "S3_21") (pintype "bidirectional"))
    )
    (net (code "346") (name "Net-(U$17-GPI03)") (class "Default")
      (node (ref "U$17") (pin "29") (pinfunction "GPI03_29") (pintype "bidirectional"))
      (node (ref "U$18") (pin "20") (pinfunction "C3_20") (pintype "bidirectional"))
    )
    (net (code "347") (name "Net-(U$17-GPI04)") (class "Default")
      (node (ref "U$17") (pin "32") (pinfunction "GPI04_32") (pintype "bidirectional"))
      (node (ref "U$18") (pin "17") (pinfunction "S5_17") (pintype "bidirectional"))
    )
    (net (code "348") (name "Net-(U$17-GPI05)") (class "Default")
      (node (ref "U$17") (pin "33") (pinfunction "GPI05_33") (pintype "bidirectional"))
      (node (ref "U$18") (pin "16") (pinfunction "C5_16") (pintype "bidirectional"))
    )
    (net (code "349") (name "Net-(U$17-ISOMD)") (class "Default")
      (node (ref "U$17") (pin "40") (pinfunction "ISOMD_40") (pintype "bidirectional"))
      (node (ref "U$18") (pin "9") (pinfunction "S9_9") (pintype "bidirectional"))
    )
    (net (code "350") (name "Net-(U$17-S1)") (class "Default")
      (node (ref "U$17") (pin "25") (pinfunction "S1_25") (pintype "bidirectional"))
      (node (ref "U$18") (pin "24") (pinfunction "C1_24") (pintype "bidirectional"))
    )
    (net (code "351") (name "Net-(U$17-SCK(IPA))") (class "Default")
      (node (ref "U$17") (pin "42") (pinfunction "SCK(IPA)_42") (pintype "bidirectional"))
      (node (ref "U$18") (pin "7") (pinfunction "S10_7") (pintype "bidirectional"))
    )
    (net (code "352") (name "Net-(U$17-SDI(ICMP))") (class "Default")
      (node (ref "U$17") (pin "43") (pinfunction "SDI(ICMP)_43") (pintype "bidirectional"))
      (node (ref "U$18") (pin "6") (pinfunction "C10_6") (pintype "bidirectional"))
    )
    (net (code "353") (name "Net-(U$17-SDO(IBIAS))") (class "Default")
      (node (ref "U$17") (pin "44") (pinfunction "SDO(IBIAS)_44") (pintype "bidirectional"))
      (node (ref "U$18") (pin "5") (pinfunction "S11_5") (pintype "bidirectional"))
    )
    (net (code "354") (name "Net-(U$17-SWTEN)") (class "Default")
      (node (ref "U$17") (pin "36") (pinfunction "SWTEN_36") (pintype "bidirectional"))
      (node (ref "U$18") (pin "13") (pinfunction "S7_13") (pintype "bidirectional"))
    )
    (net (code "355") (name "Net-(U$17-V-)") (class "Default")
      (node (ref "U$17") (pin "31") (pinfunction "V-_31") (pintype "bidirectional"))
      (node (ref "U$18") (pin "18") (pinfunction "C4_18") (pintype "bidirectional"))
    )
    (net (code "356") (name "Net-(U$17-V-**)") (class "Default")
      (node (ref "U$17") (pin "30") (pinfunction "V-**_30") (pintype "bidirectional"))
      (node (ref "U$18") (pin "19") (pinfunction "S4_19") (pintype "bidirectional"))
    )
    (net (code "357") (name "Net-(U$17-VREF1)") (class "Default")
      (node (ref "U$17") (pin "35") (pinfunction "VREF1_35") (pintype "bidirectional"))
      (node (ref "U$18") (pin "14") (pinfunction "C6_14") (pintype "bidirectional"))
    )
    (net (code "358") (name "Net-(U$17-VREF2)") (class "Default")
      (node (ref "U$17") (pin "34") (pinfunction "VREF2_34") (pintype "bidirectional"))
      (node (ref "U$18") (pin "15") (pinfunction "S6_15") (pintype "bidirectional"))
    )
    (net (code "359") (name "Net-(U$17-VREG)") (class "Default")
      (node (ref "U$17") (pin "37") (pinfunction "VREG_37") (pintype "bidirectional"))
      (node (ref "U$18") (pin "12") (pinfunction "C7_12") (pintype "bidirectional"))
    )
    (net (code "360") (name "Net-(U$17-WDT)") (class "Default")
      (node (ref "U$17") (pin "39") (pinfunction "WDT_39") (pintype "bidirectional"))
      (node (ref "U$18") (pin "10") (pinfunction "C8_10") (pintype "bidirectional"))
    )
    (net (code "361") (name "Net-(U$19-A0)") (class "Default")
      (node (ref "U$19") (pin "45") (pinfunction "A0_45") (pintype "bidirectional"))
      (node (ref "U$20") (pin "4") (pinfunction "C11_4") (pintype "bidirectional"))
    )
    (net (code "362") (name "Net-(U$19-A1)") (class "Default")
      (node (ref "U$19") (pin "46") (pinfunction "A1_46") (pintype "bidirectional"))
      (node (ref "U$20") (pin "3") (pinfunction "S12_3") (pintype "bidirectional"))
    )
    (net (code "363") (name "Net-(U$19-A2)") (class "Default")
      (node (ref "U$19") (pin "47") (pinfunction "A2_47") (pintype "bidirectional"))
      (node (ref "U$20") (pin "2") (pinfunction "C12_2") (pintype "bidirectional"))
    )
    (net (code "364") (name "Net-(U$19-A3)") (class "Default")
      (node (ref "U$19") (pin "48") (pinfunction "A3_48") (pintype "bidirectional"))
      (node (ref "U$20") (pin "1") (pinfunction "V+_1") (pintype "bidirectional"))
    )
    (net (code "365") (name "Net-(U$19-C0)") (class "Default")
      (node (ref "U$19") (pin "26") (pinfunction "C0_26") (pintype "bidirectional"))
      (node (ref "U$20") (pin "23") (pinfunction "S2_23") (pintype "bidirectional"))
    )
    (net (code "366") (name "Net-(U$19-CSB(IMA))") (class "Default")
      (node (ref "U$19") (pin "41") (pinfunction "CSB(IMA)_41") (pintype "bidirectional"))
      (node (ref "U$20") (pin "8") (pinfunction "C9_8") (pintype "bidirectional"))
    )
    (net (code "367") (name "Net-(U$19-DRIVE)") (class "Default")
      (node (ref "U$19") (pin "38") (pinfunction "DRIVE_38") (pintype "bidirectional"))
      (node (ref "U$20") (pin "11") (pinfunction "S8_11") (pintype "bidirectional"))
    )
    (net (code "368") (name "Net-(U$19-GPI01)") (class "Default")
      (node (ref "U$19") (pin "27") (pinfunction "GPI01_27") (pintype "bidirectional"))
      (node (ref "U$20") (pin "22") (pinfunction "C2_22") (pintype "bidirectional"))
    )
    (net (code "369") (name "Net-(U$19-GPI02)") (class "Default")
      (node (ref "U$19") (pin "28") (pinfunction "GPI02_28") (pintype "bidirectional"))
      (node (ref "U$20") (pin "21") (pinfunction "S3_21") (pintype "bidirectional"))
    )
    (net (code "370") (name "Net-(U$19-GPI03)") (class "Default")
      (node (ref "U$19") (pin "29") (pinfunction "GPI03_29") (pintype "bidirectional"))
      (node (ref "U$20") (pin "20") (pinfunction "C3_20") (pintype "bidirectional"))
    )
    (net (code "371") (name "Net-(U$19-GPI04)") (class "Default")
      (node (ref "U$19") (pin "32") (pinfunction "GPI04_32") (pintype "bidirectional"))
      (node (ref "U$20") (pin "17") (pinfunction "S5_17") (pintype "bidirectional"))
    )
    (net (code "372") (name "Net-(U$19-GPI05)") (class "Default")
      (node (ref "U$19") (pin "33") (pinfunction "GPI05_33") (pintype "bidirectional"))
      (node (ref "U$20") (pin "16") (pinfunction "C5_16") (pintype "bidirectional"))
    )
    (net (code "373") (name "Net-(U$19-ISOMD)") (class "Default")
      (node (ref "U$19") (pin "40") (pinfunction "ISOMD_40") (pintype "bidirectional"))
      (node (ref "U$20") (pin "9") (pinfunction "S9_9") (pintype "bidirectional"))
    )
    (net (code "374") (name "Net-(U$19-S1)") (class "Default")
      (node (ref "U$19") (pin "25") (pinfunction "S1_25") (pintype "bidirectional"))
      (node (ref "U$20") (pin "24") (pinfunction "C1_24") (pintype "bidirectional"))
    )
    (net (code "375") (name "Net-(U$19-SCK(IPA))") (class "Default")
      (node (ref "U$19") (pin "42") (pinfunction "SCK(IPA)_42") (pintype "bidirectional"))
      (node (ref "U$20") (pin "7") (pinfunction "S10_7") (pintype "bidirectional"))
    )
    (net (code "376") (name "Net-(U$19-SDI(ICMP))") (class "Default")
      (node (ref "U$19") (pin "43") (pinfunction "SDI(ICMP)_43") (pintype "bidirectional"))
      (node (ref "U$20") (pin "6") (pinfunction "C10_6") (pintype "bidirectional"))
    )
    (net (code "377") (name "Net-(U$19-SDO(IBIAS))") (class "Default")
      (node (ref "U$19") (pin "44") (pinfunction "SDO(IBIAS)_44") (pintype "bidirectional"))
      (node (ref "U$20") (pin "5") (pinfunction "S11_5") (pintype "bidirectional"))
    )
    (net (code "378") (name "Net-(U$19-SWTEN)") (class "Default")
      (node (ref "U$19") (pin "36") (pinfunction "SWTEN_36") (pintype "bidirectional"))
      (node (ref "U$20") (pin "13") (pinfunction "S7_13") (pintype "bidirectional"))
    )
    (net (code "379") (name "Net-(U$19-V-)") (class "Default")
      (node (ref "U$19") (pin "31") (pinfunction "V-_31") (pintype "bidirectional"))
      (node (ref "U$20") (pin "18") (pinfunction "C4_18") (pintype "bidirectional"))
    )
    (net (code "380") (name "Net-(U$19-V-**)") (class "Default")
      (node (ref "U$19") (pin "30") (pinfunction "V-**_30") (pintype "bidirectional"))
      (node (ref "U$20") (pin "19") (pinfunction "S4_19") (pintype "bidirectional"))
    )
    (net (code "381") (name "Net-(U$19-VREF1)") (class "Default")
      (node (ref "U$19") (pin "35") (pinfunction "VREF1_35") (pintype "bidirectional"))
      (node (ref "U$20") (pin "14") (pinfunction "C6_14") (pintype "bidirectional"))
    )
    (net (code "382") (name "Net-(U$19-VREF2)") (class "Default")
      (node (ref "U$19") (pin "34") (pinfunction "VREF2_34") (pintype "bidirectional"))
      (node (ref "U$20") (pin "15") (pinfunction "S6_15") (pintype "bidirectional"))
    )
    (net (code "383") (name "Net-(U$19-VREG)") (class "Default")
      (node (ref "U$19") (pin "37") (pinfunction "VREG_37") (pintype "bidirectional"))
      (node (ref "U$20") (pin "12") (pinfunction "C7_12") (pintype "bidirectional"))
    )
    (net (code "384") (name "Net-(U$19-WDT)") (class "Default")
      (node (ref "U$19") (pin "39") (pinfunction "WDT_39") (pintype "bidirectional"))
      (node (ref "U$20") (pin "10") (pinfunction "C8_10") (pintype "bidirectional"))
    )
    (net (code "385") (name "Net-(U$20-A0)") (class "Default")
      (node (ref "U$20") (pin "45") (pinfunction "A0_45") (pintype "bidirectional"))
      (node (ref "U$21") (pin "4") (pinfunction "C11_4") (pintype "bidirectional"))
    )
    (net (code "386") (name "Net-(U$20-A1)") (class "Default")
      (node (ref "U$20") (pin "46") (pinfunction "A1_46") (pintype "bidirectional"))
      (node (ref "U$21") (pin "3") (pinfunction "S12_3") (pintype "bidirectional"))
    )
    (net (code "387") (name "Net-(U$20-A2)") (class "Default")
      (node (ref "U$20") (pin "47") (pinfunction "A2_47") (pintype "bidirectional"))
      (node (ref "U$21") (pin "2") (pinfunction "C12_2") (pintype "bidirectional"))
    )
    (net (code "388") (name "Net-(U$20-A3)") (class "Default")
      (node (ref "U$20") (pin "48") (pinfunction "A3_48") (pintype "bidirectional"))
      (node (ref "U$21") (pin "1") (pinfunction "V+_1") (pintype "bidirectional"))
    )
    (net (code "389") (name "Net-(U$20-C0)") (class "Default")
      (node (ref "U$20") (pin "26") (pinfunction "C0_26") (pintype "bidirectional"))
      (node (ref "U$21") (pin "23") (pinfunction "S2_23") (pintype "bidirectional"))
    )
    (net (code "390") (name "Net-(U$20-CSB(IMA))") (class "Default")
      (node (ref "U$20") (pin "41") (pinfunction "CSB(IMA)_41") (pintype "bidirectional"))
      (node (ref "U$21") (pin "8") (pinfunction "C9_8") (pintype "bidirectional"))
    )
    (net (code "391") (name "Net-(U$20-DRIVE)") (class "Default")
      (node (ref "U$20") (pin "38") (pinfunction "DRIVE_38") (pintype "bidirectional"))
      (node (ref "U$21") (pin "11") (pinfunction "S8_11") (pintype "bidirectional"))
    )
    (net (code "392") (name "Net-(U$20-GPI01)") (class "Default")
      (node (ref "U$20") (pin "27") (pinfunction "GPI01_27") (pintype "bidirectional"))
      (node (ref "U$21") (pin "22") (pinfunction "C2_22") (pintype "bidirectional"))
    )
    (net (code "393") (name "Net-(U$20-GPI02)") (class "Default")
      (node (ref "U$20") (pin "28") (pinfunction "GPI02_28") (pintype "bidirectional"))
      (node (ref "U$21") (pin "21") (pinfunction "S3_21") (pintype "bidirectional"))
    )
    (net (code "394") (name "Net-(U$20-GPI03)") (class "Default")
      (node (ref "U$20") (pin "29") (pinfunction "GPI03_29") (pintype "bidirectional"))
      (node (ref "U$21") (pin "20") (pinfunction "C3_20") (pintype "bidirectional"))
    )
    (net (code "395") (name "Net-(U$20-GPI04)") (class "Default")
      (node (ref "U$20") (pin "32") (pinfunction "GPI04_32") (pintype "bidirectional"))
      (node (ref "U$21") (pin "17") (pinfunction "S5_17") (pintype "bidirectional"))
    )
    (net (code "396") (name "Net-(U$20-GPI05)") (class "Default")
      (node (ref "U$20") (pin "33") (pinfunction "GPI05_33") (pintype "bidirectional"))
      (node (ref "U$21") (pin "16") (pinfunction "C5_16") (pintype "bidirectional"))
    )
    (net (code "397") (name "Net-(U$20-ISOMD)") (class "Default")
      (node (ref "U$20") (pin "40") (pinfunction "ISOMD_40") (pintype "bidirectional"))
      (node (ref "U$21") (pin "9") (pinfunction "S9_9") (pintype "bidirectional"))
    )
    (net (code "398") (name "Net-(U$20-S1)") (class "Default")
      (node (ref "U$20") (pin "25") (pinfunction "S1_25") (pintype "bidirectional"))
      (node (ref "U$21") (pin "24") (pinfunction "C1_24") (pintype "bidirectional"))
    )
    (net (code "399") (name "Net-(U$20-SCK(IPA))") (class "Default")
      (node (ref "U$20") (pin "42") (pinfunction "SCK(IPA)_42") (pintype "bidirectional"))
      (node (ref "U$21") (pin "7") (pinfunction "S10_7") (pintype "bidirectional"))
    )
    (net (code "400") (name "Net-(U$20-SDI(ICMP))") (class "Default")
      (node (ref "U$20") (pin "43") (pinfunction "SDI(ICMP)_43") (pintype "bidirectional"))
      (node (ref "U$21") (pin "6") (pinfunction "C10_6") (pintype "bidirectional"))
    )
    (net (code "401") (name "Net-(U$20-SDO(IBIAS))") (class "Default")
      (node (ref "U$20") (pin "44") (pinfunction "SDO(IBIAS)_44") (pintype "bidirectional"))
      (node (ref "U$21") (pin "5") (pinfunction "S11_5") (pintype "bidirectional"))
    )
    (net (code "402") (name "Net-(U$20-SWTEN)") (class "Default")
      (node (ref "U$20") (pin "36") (pinfunction "SWTEN_36") (pintype "bidirectional"))
      (node (ref "U$21") (pin "13") (pinfunction "S7_13") (pintype "bidirectional"))
    )
    (net (code "403") (name "Net-(U$20-V-)") (class "Default")
      (node (ref "U$20") (pin "31") (pinfunction "V-_31") (pintype "bidirectional"))
      (node (ref "U$21") (pin "18") (pinfunction "C4_18") (pintype "bidirectional"))
    )
    (net (code "404") (name "Net-(U$20-V-**)") (class "Default")
      (node (ref "U$20") (pin "30") (pinfunction "V-**_30") (pintype "bidirectional"))
      (node (ref "U$21") (pin "19") (pinfunction "S4_19") (pintype "bidirectional"))
    )
    (net (code "405") (name "Net-(U$20-VREF1)") (class "Default")
      (node (ref "U$20") (pin "35") (pinfunction "VREF1_35") (pintype "bidirectional"))
      (node (ref "U$21") (pin "14") (pinfunction "C6_14") (pintype "bidirectional"))
    )
    (net (code "406") (name "Net-(U$20-VREF2)") (class "Default")
      (node (ref "U$20") (pin "34") (pinfunction "VREF2_34") (pintype "bidirectional"))
      (node (ref "U$21") (pin "15") (pinfunction "S6_15") (pintype "bidirectional"))
    )
    (net (code "407") (name "Net-(U$20-VREG)") (class "Default")
      (node (ref "U$20") (pin "37") (pinfunction "VREG_37") (pintype "bidirectional"))
      (node (ref "U$21") (pin "12") (pinfunction "C7_12") (pintype "bidirectional"))
    )
    (net (code "408") (name "Net-(U$20-WDT)") (class "Default")
      (node (ref "U$20") (pin "39") (pinfunction "WDT_39") (pintype "bidirectional"))
      (node (ref "U$21") (pin "10") (pinfunction "C8_10") (pintype "bidirectional"))
    )
    (net (code "409") (name "Net-(U$21-A0)") (class "Default")
      (node (ref "U$21") (pin "45") (pinfunction "A0_45") (pintype "bidirectional"))
      (node (ref "U$22") (pin "4") (pinfunction "C11_4") (pintype "bidirectional"))
    )
    (net (code "410") (name "Net-(U$21-A1)") (class "Default")
      (node (ref "U$21") (pin "46") (pinfunction "A1_46") (pintype "bidirectional"))
      (node (ref "U$22") (pin "3") (pinfunction "S12_3") (pintype "bidirectional"))
    )
    (net (code "411") (name "Net-(U$21-A2)") (class "Default")
      (node (ref "U$21") (pin "47") (pinfunction "A2_47") (pintype "bidirectional"))
      (node (ref "U$22") (pin "2") (pinfunction "C12_2") (pintype "bidirectional"))
    )
    (net (code "412") (name "Net-(U$21-A3)") (class "Default")
      (node (ref "U$21") (pin "48") (pinfunction "A3_48") (pintype "bidirectional"))
      (node (ref "U$22") (pin "1") (pinfunction "V+_1") (pintype "bidirectional"))
    )
    (net (code "413") (name "Net-(U$21-C0)") (class "Default")
      (node (ref "U$21") (pin "26") (pinfunction "C0_26") (pintype "bidirectional"))
      (node (ref "U$22") (pin "23") (pinfunction "S2_23") (pintype "bidirectional"))
    )
    (net (code "414") (name "Net-(U$21-CSB(IMA))") (class "Default")
      (node (ref "U$21") (pin "41") (pinfunction "CSB(IMA)_41") (pintype "bidirectional"))
      (node (ref "U$22") (pin "8") (pinfunction "C9_8") (pintype "bidirectional"))
    )
    (net (code "415") (name "Net-(U$21-DRIVE)") (class "Default")
      (node (ref "U$21") (pin "38") (pinfunction "DRIVE_38") (pintype "bidirectional"))
      (node (ref "U$22") (pin "11") (pinfunction "S8_11") (pintype "bidirectional"))
    )
    (net (code "416") (name "Net-(U$21-GPI01)") (class "Default")
      (node (ref "U$21") (pin "27") (pinfunction "GPI01_27") (pintype "bidirectional"))
      (node (ref "U$22") (pin "22") (pinfunction "C2_22") (pintype "bidirectional"))
    )
    (net (code "417") (name "Net-(U$21-GPI02)") (class "Default")
      (node (ref "U$21") (pin "28") (pinfunction "GPI02_28") (pintype "bidirectional"))
      (node (ref "U$22") (pin "21") (pinfunction "S3_21") (pintype "bidirectional"))
    )
    (net (code "418") (name "Net-(U$21-GPI03)") (class "Default")
      (node (ref "U$21") (pin "29") (pinfunction "GPI03_29") (pintype "bidirectional"))
      (node (ref "U$22") (pin "20") (pinfunction "C3_20") (pintype "bidirectional"))
    )
    (net (code "419") (name "Net-(U$21-GPI04)") (class "Default")
      (node (ref "U$21") (pin "32") (pinfunction "GPI04_32") (pintype "bidirectional"))
      (node (ref "U$22") (pin "17") (pinfunction "S5_17") (pintype "bidirectional"))
    )
    (net (code "420") (name "Net-(U$21-GPI05)") (class "Default")
      (node (ref "U$21") (pin "33") (pinfunction "GPI05_33") (pintype "bidirectional"))
      (node (ref "U$22") (pin "16") (pinfunction "C5_16") (pintype "bidirectional"))
    )
    (net (code "421") (name "Net-(U$21-ISOMD)") (class "Default")
      (node (ref "U$21") (pin "40") (pinfunction "ISOMD_40") (pintype "bidirectional"))
      (node (ref "U$22") (pin "9") (pinfunction "S9_9") (pintype "bidirectional"))
    )
    (net (code "422") (name "Net-(U$21-S1)") (class "Default")
      (node (ref "U$21") (pin "25") (pinfunction "S1_25") (pintype "bidirectional"))
      (node (ref "U$22") (pin "24") (pinfunction "C1_24") (pintype "bidirectional"))
    )
    (net (code "423") (name "Net-(U$21-SCK(IPA))") (class "Default")
      (node (ref "U$21") (pin "42") (pinfunction "SCK(IPA)_42") (pintype "bidirectional"))
      (node (ref "U$22") (pin "7") (pinfunction "S10_7") (pintype "bidirectional"))
    )
    (net (code "424") (name "Net-(U$21-SDI(ICMP))") (class "Default")
      (node (ref "U$21") (pin "43") (pinfunction "SDI(ICMP)_43") (pintype "bidirectional"))
      (node (ref "U$22") (pin "6") (pinfunction "C10_6") (pintype "bidirectional"))
    )
    (net (code "425") (name "Net-(U$21-SDO(IBIAS))") (class "Default")
      (node (ref "U$21") (pin "44") (pinfunction "SDO(IBIAS)_44") (pintype "bidirectional"))
      (node (ref "U$22") (pin "5") (pinfunction "S11_5") (pintype "bidirectional"))
    )
    (net (code "426") (name "Net-(U$21-SWTEN)") (class "Default")
      (node (ref "U$21") (pin "36") (pinfunction "SWTEN_36") (pintype "bidirectional"))
      (node (ref "U$22") (pin "13") (pinfunction "S7_13") (pintype "bidirectional"))
    )
    (net (code "427") (name "Net-(U$21-V-)") (class "Default")
      (node (ref "U$21") (pin "31") (pinfunction "V-_31") (pintype "bidirectional"))
      (node (ref "U$22") (pin "18") (pinfunction "C4_18") (pintype "bidirectional"))
    )
    (net (code "428") (name "Net-(U$21-V-**)") (class "Default")
      (node (ref "U$21") (pin "30") (pinfunction "V-**_30") (pintype "bidirectional"))
      (node (ref "U$22") (pin "19") (pinfunction "S4_19") (pintype "bidirectional"))
    )
    (net (code "429") (name "Net-(U$21-VREF1)") (class "Default")
      (node (ref "U$21") (pin "35") (pinfunction "VREF1_35") (pintype "bidirectional"))
      (node (ref "U$22") (pin "14") (pinfunction "C6_14") (pintype "bidirectional"))
    )
    (net (code "430") (name "Net-(U$21-VREF2)") (class "Default")
      (node (ref "U$21") (pin "34") (pinfunction "VREF2_34") (pintype "bidirectional"))
      (node (ref "U$22") (pin "15") (pinfunction "S6_15") (pintype "bidirectional"))
    )
    (net (code "431") (name "Net-(U$21-VREG)") (class "Default")
      (node (ref "U$21") (pin "37") (pinfunction "VREG_37") (pintype "bidirectional"))
      (node (ref "U$22") (pin "12") (pinfunction "C7_12") (pintype "bidirectional"))
    )
    (net (code "432") (name "Net-(U$21-WDT)") (class "Default")
      (node (ref "U$21") (pin "39") (pinfunction "WDT_39") (pintype "bidirectional"))
      (node (ref "U$22") (pin "10") (pinfunction "C8_10") (pintype "bidirectional"))
    )
    (net (code "433") (name "Net-(U$22-A0)") (class "Default")
      (node (ref "U$22") (pin "45") (pinfunction "A0_45") (pintype "bidirectional"))
      (node (ref "U$23") (pin "4") (pinfunction "C11_4") (pintype "bidirectional"))
    )
    (net (code "434") (name "Net-(U$22-A1)") (class "Default")
      (node (ref "U$22") (pin "46") (pinfunction "A1_46") (pintype "bidirectional"))
      (node (ref "U$23") (pin "3") (pinfunction "S12_3") (pintype "bidirectional"))
    )
    (net (code "435") (name "Net-(U$22-A2)") (class "Default")
      (node (ref "U$22") (pin "47") (pinfunction "A2_47") (pintype "bidirectional"))
      (node (ref "U$23") (pin "2") (pinfunction "C12_2") (pintype "bidirectional"))
    )
    (net (code "436") (name "Net-(U$22-A3)") (class "Default")
      (node (ref "U$22") (pin "48") (pinfunction "A3_48") (pintype "bidirectional"))
      (node (ref "U$23") (pin "1") (pinfunction "V+_1") (pintype "bidirectional"))
    )
    (net (code "437") (name "Net-(U$22-C0)") (class "Default")
      (node (ref "U$22") (pin "26") (pinfunction "C0_26") (pintype "bidirectional"))
      (node (ref "U$23") (pin "23") (pinfunction "S2_23") (pintype "bidirectional"))
    )
    (net (code "438") (name "Net-(U$22-CSB(IMA))") (class "Default")
      (node (ref "U$22") (pin "41") (pinfunction "CSB(IMA)_41") (pintype "bidirectional"))
      (node (ref "U$23") (pin "8") (pinfunction "C9_8") (pintype "bidirectional"))
    )
    (net (code "439") (name "Net-(U$22-DRIVE)") (class "Default")
      (node (ref "U$22") (pin "38") (pinfunction "DRIVE_38") (pintype "bidirectional"))
      (node (ref "U$23") (pin "11") (pinfunction "S8_11") (pintype "bidirectional"))
    )
    (net (code "440") (name "Net-(U$22-GPI01)") (class "Default")
      (node (ref "U$22") (pin "27") (pinfunction "GPI01_27") (pintype "bidirectional"))
      (node (ref "U$23") (pin "22") (pinfunction "C2_22") (pintype "bidirectional"))
    )
    (net (code "441") (name "Net-(U$22-GPI02)") (class "Default")
      (node (ref "U$22") (pin "28") (pinfunction "GPI02_28") (pintype "bidirectional"))
      (node (ref "U$23") (pin "21") (pinfunction "S3_21") (pintype "bidirectional"))
    )
    (net (code "442") (name "Net-(U$22-GPI03)") (class "Default")
      (node (ref "U$22") (pin "29") (pinfunction "GPI03_29") (pintype "bidirectional"))
      (node (ref "U$23") (pin "20") (pinfunction "C3_20") (pintype "bidirectional"))
    )
    (net (code "443") (name "Net-(U$22-GPI04)") (class "Default")
      (node (ref "U$22") (pin "32") (pinfunction "GPI04_32") (pintype "bidirectional"))
      (node (ref "U$23") (pin "17") (pinfunction "S5_17") (pintype "bidirectional"))
    )
    (net (code "444") (name "Net-(U$22-GPI05)") (class "Default")
      (node (ref "U$22") (pin "33") (pinfunction "GPI05_33") (pintype "bidirectional"))
      (node (ref "U$23") (pin "16") (pinfunction "C5_16") (pintype "bidirectional"))
    )
    (net (code "445") (name "Net-(U$22-ISOMD)") (class "Default")
      (node (ref "U$22") (pin "40") (pinfunction "ISOMD_40") (pintype "bidirectional"))
      (node (ref "U$23") (pin "9") (pinfunction "S9_9") (pintype "bidirectional"))
    )
    (net (code "446") (name "Net-(U$22-S1)") (class "Default")
      (node (ref "U$22") (pin "25") (pinfunction "S1_25") (pintype "bidirectional"))
      (node (ref "U$23") (pin "24") (pinfunction "C1_24") (pintype "bidirectional"))
    )
    (net (code "447") (name "Net-(U$22-SCK(IPA))") (class "Default")
      (node (ref "U$22") (pin "42") (pinfunction "SCK(IPA)_42") (pintype "bidirectional"))
      (node (ref "U$23") (pin "7") (pinfunction "S10_7") (pintype "bidirectional"))
    )
    (net (code "448") (name "Net-(U$22-SDI(ICMP))") (class "Default")
      (node (ref "U$22") (pin "43") (pinfunction "SDI(ICMP)_43") (pintype "bidirectional"))
      (node (ref "U$23") (pin "6") (pinfunction "C10_6") (pintype "bidirectional"))
    )
    (net (code "449") (name "Net-(U$22-SDO(IBIAS))") (class "Default")
      (node (ref "U$22") (pin "44") (pinfunction "SDO(IBIAS)_44") (pintype "bidirectional"))
      (node (ref "U$23") (pin "5") (pinfunction "S11_5") (pintype "bidirectional"))
    )
    (net (code "450") (name "Net-(U$22-SWTEN)") (class "Default")
      (node (ref "U$22") (pin "36") (pinfunction "SWTEN_36") (pintype "bidirectional"))
      (node (ref "U$23") (pin "13") (pinfunction "S7_13") (pintype "bidirectional"))
    )
    (net (code "451") (name "Net-(U$22-V-)") (class "Default")
      (node (ref "U$22") (pin "31") (pinfunction "V-_31") (pintype "bidirectional"))
      (node (ref "U$23") (pin "18") (pinfunction "C4_18") (pintype "bidirectional"))
    )
    (net (code "452") (name "Net-(U$22-V-**)") (class "Default")
      (node (ref "U$22") (pin "30") (pinfunction "V-**_30") (pintype "bidirectional"))
      (node (ref "U$23") (pin "19") (pinfunction "S4_19") (pintype "bidirectional"))
    )
    (net (code "453") (name "Net-(U$22-VREF1)") (class "Default")
      (node (ref "U$22") (pin "35") (pinfunction "VREF1_35") (pintype "bidirectional"))
      (node (ref "U$23") (pin "14") (pinfunction "C6_14") (pintype "bidirectional"))
    )
    (net (code "454") (name "Net-(U$22-VREF2)") (class "Default")
      (node (ref "U$22") (pin "34") (pinfunction "VREF2_34") (pintype "bidirectional"))
      (node (ref "U$23") (pin "15") (pinfunction "S6_15") (pintype "bidirectional"))
    )
    (net (code "455") (name "Net-(U$22-VREG)") (class "Default")
      (node (ref "U$22") (pin "37") (pinfunction "VREG_37") (pintype "bidirectional"))
      (node (ref "U$23") (pin "12") (pinfunction "C7_12") (pintype "bidirectional"))
    )
    (net (code "456") (name "Net-(U$22-WDT)") (class "Default")
      (node (ref "U$22") (pin "39") (pinfunction "WDT_39") (pintype "bidirectional"))
      (node (ref "U$23") (pin "10") (pinfunction "C8_10") (pintype "bidirectional"))
    )
    (net (code "457") (name "Net-(U$23-A0)") (class "Default")
      (node (ref "U$23") (pin "45") (pinfunction "A0_45") (pintype "bidirectional"))
      (node (ref "U$24") (pin "4") (pinfunction "C11_4") (pintype "bidirectional"))
    )
    (net (code "458") (name "Net-(U$23-A1)") (class "Default")
      (node (ref "U$23") (pin "46") (pinfunction "A1_46") (pintype "bidirectional"))
      (node (ref "U$24") (pin "3") (pinfunction "S12_3") (pintype "bidirectional"))
    )
    (net (code "459") (name "Net-(U$23-A2)") (class "Default")
      (node (ref "U$23") (pin "47") (pinfunction "A2_47") (pintype "bidirectional"))
      (node (ref "U$24") (pin "2") (pinfunction "C12_2") (pintype "bidirectional"))
    )
    (net (code "460") (name "Net-(U$23-A3)") (class "Default")
      (node (ref "U$23") (pin "48") (pinfunction "A3_48") (pintype "bidirectional"))
      (node (ref "U$24") (pin "1") (pinfunction "V+_1") (pintype "bidirectional"))
    )
    (net (code "461") (name "Net-(U$23-C0)") (class "Default")
      (node (ref "U$23") (pin "26") (pinfunction "C0_26") (pintype "bidirectional"))
      (node (ref "U$24") (pin "23") (pinfunction "S2_23") (pintype "bidirectional"))
    )
    (net (code "462") (name "Net-(U$23-CSB(IMA))") (class "Default")
      (node (ref "U$23") (pin "41") (pinfunction "CSB(IMA)_41") (pintype "bidirectional"))
      (node (ref "U$24") (pin "8") (pinfunction "C9_8") (pintype "bidirectional"))
    )
    (net (code "463") (name "Net-(U$23-DRIVE)") (class "Default")
      (node (ref "U$23") (pin "38") (pinfunction "DRIVE_38") (pintype "bidirectional"))
      (node (ref "U$24") (pin "11") (pinfunction "S8_11") (pintype "bidirectional"))
    )
    (net (code "464") (name "Net-(U$23-GPI01)") (class "Default")
      (node (ref "U$23") (pin "27") (pinfunction "GPI01_27") (pintype "bidirectional"))
      (node (ref "U$24") (pin "22") (pinfunction "C2_22") (pintype "bidirectional"))
    )
    (net (code "465") (name "Net-(U$23-GPI02)") (class "Default")
      (node (ref "U$23") (pin "28") (pinfunction "GPI02_28") (pintype "bidirectional"))
      (node (ref "U$24") (pin "21") (pinfunction "S3_21") (pintype "bidirectional"))
    )
    (net (code "466") (name "Net-(U$23-GPI03)") (class "Default")
      (node (ref "U$23") (pin "29") (pinfunction "GPI03_29") (pintype "bidirectional"))
      (node (ref "U$24") (pin "20") (pinfunction "C3_20") (pintype "bidirectional"))
    )
    (net (code "467") (name "Net-(U$23-GPI04)") (class "Default")
      (node (ref "U$23") (pin "32") (pinfunction "GPI04_32") (pintype "bidirectional"))
      (node (ref "U$24") (pin "17") (pinfunction "S5_17") (pintype "bidirectional"))
    )
    (net (code "468") (name "Net-(U$23-GPI05)") (class "Default")
      (node (ref "U$23") (pin "33") (pinfunction "GPI05_33") (pintype "bidirectional"))
      (node (ref "U$24") (pin "16") (pinfunction "C5_16") (pintype "bidirectional"))
    )
    (net (code "469") (name "Net-(U$23-ISOMD)") (class "Default")
      (node (ref "U$23") (pin "40") (pinfunction "ISOMD_40") (pintype "bidirectional"))
      (node (ref "U$24") (pin "9") (pinfunction "S9_9") (pintype "bidirectional"))
    )
    (net (code "470") (name "Net-(U$23-S1)") (class "Default")
      (node (ref "U$23") (pin "25") (pinfunction "S1_25") (pintype "bidirectional"))
      (node (ref "U$24") (pin "24") (pinfunction "C1_24") (pintype "bidirectional"))
    )
    (net (code "471") (name "Net-(U$23-SCK(IPA))") (class "Default")
      (node (ref "U$23") (pin "42") (pinfunction "SCK(IPA)_42") (pintype "bidirectional"))
      (node (ref "U$24") (pin "7") (pinfunction "S10_7") (pintype "bidirectional"))
    )
    (net (code "472") (name "Net-(U$23-SDI(ICMP))") (class "Default")
      (node (ref "U$23") (pin "43") (pinfunction "SDI(ICMP)_43") (pintype "bidirectional"))
      (node (ref "U$24") (pin "6") (pinfunction "C10_6") (pintype "bidirectional"))
    )
    (net (code "473") (name "Net-(U$23-SDO(IBIAS))") (class "Default")
      (node (ref "U$23") (pin "44") (pinfunction "SDO(IBIAS)_44") (pintype "bidirectional"))
      (node (ref "U$24") (pin "5") (pinfunction "S11_5") (pintype "bidirectional"))
    )
    (net (code "474") (name "Net-(U$23-SWTEN)") (class "Default")
      (node (ref "U$23") (pin "36") (pinfunction "SWTEN_36") (pintype "bidirectional"))
      (node (ref "U$24") (pin "13") (pinfunction "S7_13") (pintype "bidirectional"))
    )
    (net (code "475") (name "Net-(U$23-V-)") (class "Default")
      (node (ref "U$23") (pin "31") (pinfunction "V-_31") (pintype "bidirectional"))
      (node (ref "U$24") (pin "18") (pinfunction "C4_18") (pintype "bidirectional"))
    )
    (net (code "476") (name "Net-(U$23-V-**)") (class "Default")
      (node (ref "U$23") (pin "30") (pinfunction "V-**_30") (pintype "bidirectional"))
      (node (ref "U$24") (pin "19") (pinfunction "S4_19") (pintype "bidirectional"))
    )
    (net (code "477") (name "Net-(U$23-VREF1)") (class "Default")
      (node (ref "U$23") (pin "35") (pinfunction "VREF1_35") (pintype "bidirectional"))
      (node (ref "U$24") (pin "14") (pinfunction "C6_14") (pintype "bidirectional"))
    )
    (net (code "478") (name "Net-(U$23-VREF2)") (class "Default")
      (node (ref "U$23") (pin "34") (pinfunction "VREF2_34") (pintype "bidirectional"))
      (node (ref "U$24") (pin "15") (pinfunction "S6_15") (pintype "bidirectional"))
    )
    (net (code "479") (name "Net-(U$23-VREG)") (class "Default")
      (node (ref "U$23") (pin "37") (pinfunction "VREG_37") (pintype "bidirectional"))
      (node (ref "U$24") (pin "12") (pinfunction "C7_12") (pintype "bidirectional"))
    )
    (net (code "480") (name "Net-(U$23-WDT)") (class "Default")
      (node (ref "U$23") (pin "39") (pinfunction "WDT_39") (pintype "bidirectional"))
      (node (ref "U$24") (pin "10") (pinfunction "C8_10") (pintype "bidirectional"))
    )
    (net (code "481") (name "unconnected-(U$1-C1-Pad24)") (class "Default")
      (node (ref "U$1") (pin "24") (pinfunction "C1_24") (pintype "bidirectional"))
    )
    (net (code "482") (name "unconnected-(U$1-C2-Pad22)") (class "Default")
      (node (ref "U$1") (pin "22") (pinfunction "C2_22") (pintype "bidirectional"))
    )
    (net (code "483") (name "unconnected-(U$1-C3-Pad20)") (class "Default")
      (node (ref "U$1") (pin "20") (pinfunction "C3_20") (pintype "bidirectional"))
    )
    (net (code "484") (name "unconnected-(U$1-C4-Pad18)") (class "Default")
      (node (ref "U$1") (pin "18") (pinfunction "C4_18") (pintype "bidirectional"))
    )
    (net (code "485") (name "unconnected-(U$1-C5-Pad16)") (class "Default")
      (node (ref "U$1") (pin "16") (pinfunction "C5_16") (pintype "bidirectional"))
    )
    (net (code "486") (name "unconnected-(U$1-C6-Pad14)") (class "Default")
      (node (ref "U$1") (pin "14") (pinfunction "C6_14") (pintype "bidirectional"))
    )
    (net (code "487") (name "unconnected-(U$1-C7-Pad12)") (class "Default")
      (node (ref "U$1") (pin "12") (pinfunction "C7_12") (pintype "bidirectional"))
    )
    (net (code "488") (name "unconnected-(U$1-C8-Pad10)") (class "Default")
      (node (ref "U$1") (pin "10") (pinfunction "C8_10") (pintype "bidirectional"))
    )
    (net (code "489") (name "unconnected-(U$1-C9-Pad8)") (class "Default")
      (node (ref "U$1") (pin "8") (pinfunction "C9_8") (pintype "bidirectional"))
    )
    (net (code "490") (name "unconnected-(U$1-C10-Pad6)") (class "Default")
      (node (ref "U$1") (pin "6") (pinfunction "C10_6") (pintype "bidirectional"))
    )
    (net (code "491") (name "unconnected-(U$1-C11-Pad4)") (class "Default")
      (node (ref "U$1") (pin "4") (pinfunction "C11_4") (pintype "bidirectional"))
    )
    (net (code "492") (name "unconnected-(U$1-C12-Pad2)") (class "Default")
      (node (ref "U$1") (pin "2") (pinfunction "C12_2") (pintype "bidirectional"))
    )
    (net (code "493") (name "unconnected-(U$1-S2-Pad23)") (class "Default")
      (node (ref "U$1") (pin "23") (pinfunction "S2_23") (pintype "bidirectional"))
    )
    (net (code "494") (name "unconnected-(U$1-S3-Pad21)") (class "Default")
      (node (ref "U$1") (pin "21") (pinfunction "S3_21") (pintype "bidirectional"))
    )
    (net (code "495") (name "unconnected-(U$1-S4-Pad19)") (class "Default")
      (node (ref "U$1") (pin "19") (pinfunction "S4_19") (pintype "bidirectional"))
    )
    (net (code "496") (name "unconnected-(U$1-S5-Pad17)") (class "Default")
      (node (ref "U$1") (pin "17") (pinfunction "S5_17") (pintype "bidirectional"))
    )
    (net (code "497") (name "unconnected-(U$1-S6-Pad15)") (class "Default")
      (node (ref "U$1") (pin "15") (pinfunction "S6_15") (pintype "bidirectional"))
    )
    (net (code "498") (name "unconnected-(U$1-S7-Pad13)") (class "Default")
      (node (ref "U$1") (pin "13") (pinfunction "S7_13") (pintype "bidirectional"))
    )
    (net (code "499") (name "unconnected-(U$1-S8-Pad11)") (class "Default")
      (node (ref "U$1") (pin "11") (pinfunction "S8_11") (pintype "bidirectional"))
    )
    (net (code "500") (name "unconnected-(U$1-S9-Pad9)") (class "Default")
      (node (ref "U$1") (pin "9") (pinfunction "S9_9") (pintype "bidirectional"))
    )
    (net (code "501") (name "unconnected-(U$1-S10-Pad7)") (class "Default")
      (node (ref "U$1") (pin "7") (pinfunction "S10_7") (pintype "bidirectional"))
    )
    (net (code "502") (name "unconnected-(U$1-S11-Pad5)") (class "Default")
      (node (ref "U$1") (pin "5") (pinfunction "S11_5") (pintype "bidirectional"))
    )
    (net (code "503") (name "unconnected-(U$1-S12-Pad3)") (class "Default")
      (node (ref "U$1") (pin "3") (pinfunction "S12_3") (pintype "bidirectional"))
    )
    (net (code "504") (name "unconnected-(U$1-V+-Pad1)") (class "Default")
      (node (ref "U$1") (pin "1") (pinfunction "V+_1") (pintype "bidirectional"))
    )
    (net (code "505") (name "unconnected-(U$6-A0-Pad45)") (class "Default")
      (node (ref "U$6") (pin "45") (pinfunction "A0_45") (pintype "bidirectional"))
    )
    (net (code "506") (name "unconnected-(U$6-A1-Pad46)") (class "Default")
      (node (ref "U$6") (pin "46") (pinfunction "A1_46") (pintype "bidirectional"))
    )
    (net (code "507") (name "unconnected-(U$6-A2-Pad47)") (class "Default")
      (node (ref "U$6") (pin "47") (pinfunction "A2_47") (pintype "bidirectional"))
    )
    (net (code "508") (name "unconnected-(U$6-A3-Pad48)") (class "Default")
      (node (ref "U$6") (pin "48") (pinfunction "A3_48") (pintype "bidirectional"))
    )
    (net (code "509") (name "unconnected-(U$6-C0-Pad26)") (class "Default")
      (node (ref "U$6") (pin "26") (pinfunction "C0_26") (pintype "bidirectional"))
    )
    (net (code "510") (name "unconnected-(U$6-CSB(IMA)-Pad41)") (class "Default")
      (node (ref "U$6") (pin "41") (pinfunction "CSB(IMA)_41") (pintype "bidirectional"))
    )
    (net (code "511") (name "unconnected-(U$6-DRIVE-Pad38)") (class "Default")
      (node (ref "U$6") (pin "38") (pinfunction "DRIVE_38") (pintype "bidirectional"))
    )
    (net (code "512") (name "unconnected-(U$6-GPI01-Pad27)") (class "Default")
      (node (ref "U$6") (pin "27") (pinfunction "GPI01_27") (pintype "bidirectional"))
    )
    (net (code "513") (name "unconnected-(U$6-GPI02-Pad28)") (class "Default")
      (node (ref "U$6") (pin "28") (pinfunction "GPI02_28") (pintype "bidirectional"))
    )
    (net (code "514") (name "unconnected-(U$6-GPI03-Pad29)") (class "Default")
      (node (ref "U$6") (pin "29") (pinfunction "GPI03_29") (pintype "bidirectional"))
    )
    (net (code "515") (name "unconnected-(U$6-GPI04-Pad32)") (class "Default")
      (node (ref "U$6") (pin "32") (pinfunction "GPI04_32") (pintype "bidirectional"))
    )
    (net (code "516") (name "unconnected-(U$6-GPI05-Pad33)") (class "Default")
      (node (ref "U$6") (pin "33") (pinfunction "GPI05_33") (pintype "bidirectional"))
    )
    (net (code "517") (name "unconnected-(U$6-ISOMD-Pad40)") (class "Default")
      (node (ref "U$6") (pin "40") (pinfunction "ISOMD_40") (pintype "bidirectional"))
    )
    (net (code "518") (name "unconnected-(U$6-S1-Pad25)") (class "Default")
      (node (ref "U$6") (pin "25") (pinfunction "S1_25") (pintype "bidirectional"))
    )
    (net (code "519") (name "unconnected-(U$6-SCK(IPA)-Pad42)") (class "Default")
      (node (ref "U$6") (pin "42") (pinfunction "SCK(IPA)_42") (pintype "bidirectional"))
    )
    (net (code "520") (name "unconnected-(U$6-SDI(ICMP)-Pad43)") (class "Default")
      (node (ref "U$6") (pin "43") (pinfunction "SDI(ICMP)_43") (pintype "bidirectional"))
    )
    (net (code "521") (name "unconnected-(U$6-SDO(IBIAS)-Pad44)") (class "Default")
      (node (ref "U$6") (pin "44") (pinfunction "SDO(IBIAS)_44") (pintype "bidirectional"))
    )
    (net (code "522") (name "unconnected-(U$6-SWTEN-Pad36)") (class "Default")
      (node (ref "U$6") (pin "36") (pinfunction "SWTEN_36") (pintype "bidirectional"))
    )
    (net (code "523") (name "unconnected-(U$6-V-**-Pad30)") (class "Default")
      (node (ref "U$6") (pin "30") (pinfunction "V-**_30") (pintype "bidirectional"))
    )
    (net (code "524") (name "unconnected-(U$6-V--Pad31)") (class "Default")
      (node (ref "U$6") (pin "31") (pinfunction "V-_31") (pintype "bidirectional"))
    )
    (net (code "525") (name "unconnected-(U$6-VREF1-Pad35)") (class "Default")
      (node (ref "U$6") (pin "35") (pinfunction "VREF1_35") (pintype "bidirectional"))
    )
    (net (code "526") (name "unconnected-(U$6-VREF2-Pad34)") (class "Default")
      (node (ref "U$6") (pin "34") (pinfunction "VREF2_34") (pintype "bidirectional"))
    )
    (net (code "527") (name "unconnected-(U$6-VREG-Pad37)") (class "Default")
      (node (ref "U$6") (pin "37") (pinfunction "VREG_37") (pintype "bidirectional"))
    )
    (net (code "528") (name "unconnected-(U$6-WDT-Pad39)") (class "Default")
      (node (ref "U$6") (pin "39") (pinfunction "WDT_39") (pintype "bidirectional"))
    )
    (net (code "529") (name "unconnected-(U$7-C1-Pad24)") (class "Default")
      (node (ref "U$7") (pin "24") (pinfunction "C1_24") (pintype "bidirectional"))
    )
    (net (code "530") (name "unconnected-(U$7-C2-Pad22)") (class "Default")
      (node (ref "U$7") (pin "22") (pinfunction "C2_22") (pintype "bidirectional"))
    )
    (net (code "531") (name "unconnected-(U$7-C3-Pad20)") (class "Default")
      (node (ref "U$7") (pin "20") (pinfunction "C3_20") (pintype "bidirectional"))
    )
    (net (code "532") (name "unconnected-(U$7-C4-Pad18)") (class "Default")
      (node (ref "U$7") (pin "18") (pinfunction "C4_18") (pintype "bidirectional"))
    )
    (net (code "533") (name "unconnected-(U$7-C5-Pad16)") (class "Default")
      (node (ref "U$7") (pin "16") (pinfunction "C5_16") (pintype "bidirectional"))
    )
    (net (code "534") (name "unconnected-(U$7-C6-Pad14)") (class "Default")
      (node (ref "U$7") (pin "14") (pinfunction "C6_14") (pintype "bidirectional"))
    )
    (net (code "535") (name "unconnected-(U$7-C7-Pad12)") (class "Default")
      (node (ref "U$7") (pin "12") (pinfunction "C7_12") (pintype "bidirectional"))
    )
    (net (code "536") (name "unconnected-(U$7-C8-Pad10)") (class "Default")
      (node (ref "U$7") (pin "10") (pinfunction "C8_10") (pintype "bidirectional"))
    )
    (net (code "537") (name "unconnected-(U$7-C9-Pad8)") (class "Default")
      (node (ref "U$7") (pin "8") (pinfunction "C9_8") (pintype "bidirectional"))
    )
    (net (code "538") (name "unconnected-(U$7-C10-Pad6)") (class "Default")
      (node (ref "U$7") (pin "6") (pinfunction "C10_6") (pintype "bidirectional"))
    )
    (net (code "539") (name "unconnected-(U$7-C11-Pad4)") (class "Default")
      (node (ref "U$7") (pin "4") (pinfunction "C11_4") (pintype "bidirectional"))
    )
    (net (code "540") (name "unconnected-(U$7-C12-Pad2)") (class "Default")
      (node (ref "U$7") (pin "2") (pinfunction "C12_2") (pintype "bidirectional"))
    )
    (net (code "541") (name "unconnected-(U$7-S2-Pad23)") (class "Default")
      (node (ref "U$7") (pin "23") (pinfunction "S2_23") (pintype "bidirectional"))
    )
    (net (code "542") (name "unconnected-(U$7-S3-Pad21)") (class "Default")
      (node (ref "U$7") (pin "21") (pinfunction "S3_21") (pintype "bidirectional"))
    )
    (net (code "543") (name "unconnected-(U$7-S4-Pad19)") (class "Default")
      (node (ref "U$7") (pin "19") (pinfunction "S4_19") (pintype "bidirectional"))
    )
    (net (code "544") (name "unconnected-(U$7-S5-Pad17)") (class "Default")
      (node (ref "U$7") (pin "17") (pinfunction "S5_17") (pintype "bidirectional"))
    )
    (net (code "545") (name "unconnected-(U$7-S6-Pad15)") (class "Default")
      (node (ref "U$7") (pin "15") (pinfunction "S6_15") (pintype "bidirectional"))
    )
    (net (code "546") (name "unconnected-(U$7-S7-Pad13)") (class "Default")
      (node (ref "U$7") (pin "13") (pinfunction "S7_13") (pintype "bidirectional"))
    )
    (net (code "547") (name "unconnected-(U$7-S8-Pad11)") (class "Default")
      (node (ref "U$7") (pin "11") (pinfunction "S8_11") (pintype "bidirectional"))
    )
    (net (code "548") (name "unconnected-(U$7-S9-Pad9)") (class "Default")
      (node (ref "U$7") (pin "9") (pinfunction "S9_9") (pintype "bidirectional"))
    )
    (net (code "549") (name "unconnected-(U$7-S10-Pad7)") (class "Default")
      (node (ref "U$7") (pin "7") (pinfunction "S10_7") (pintype "bidirectional"))
    )
    (net (code "550") (name "unconnected-(U$7-S11-Pad5)") (class "Default")
      (node (ref "U$7") (pin "5") (pinfunction "S11_5") (pintype "bidirectional"))
    )
    (net (code "551") (name "unconnected-(U$7-S12-Pad3)") (class "Default")
      (node (ref "U$7") (pin "3") (pinfunction "S12_3") (pintype "bidirectional"))
    )
    (net (code "552") (name "unconnected-(U$7-V+-Pad1)") (class "Default")
      (node (ref "U$7") (pin "1") (pinfunction "V+_1") (pintype "bidirectional"))
    )
    (net (code "553") (name "unconnected-(U$12-A0-Pad45)") (class "Default")
      (node (ref "U$12") (pin "45") (pinfunction "A0_45") (pintype "bidirectional"))
    )
    (net (code "554") (name "unconnected-(U$12-A1-Pad46)") (class "Default")
      (node (ref "U$12") (pin "46") (pinfunction "A1_46") (pintype "bidirectional"))
    )
    (net (code "555") (name "unconnected-(U$12-A2-Pad47)") (class "Default")
      (node (ref "U$12") (pin "47") (pinfunction "A2_47") (pintype "bidirectional"))
    )
    (net (code "556") (name "unconnected-(U$12-A3-Pad48)") (class "Default")
      (node (ref "U$12") (pin "48") (pinfunction "A3_48") (pintype "bidirectional"))
    )
    (net (code "557") (name "unconnected-(U$12-C0-Pad26)") (class "Default")
      (node (ref "U$12") (pin "26") (pinfunction "C0_26") (pintype "bidirectional"))
    )
    (net (code "558") (name "unconnected-(U$12-CSB(IMA)-Pad41)") (class "Default")
      (node (ref "U$12") (pin "41") (pinfunction "CSB(IMA)_41") (pintype "bidirectional"))
    )
    (net (code "559") (name "unconnected-(U$12-DRIVE-Pad38)") (class "Default")
      (node (ref "U$12") (pin "38") (pinfunction "DRIVE_38") (pintype "bidirectional"))
    )
    (net (code "560") (name "unconnected-(U$12-GPI01-Pad27)") (class "Default")
      (node (ref "U$12") (pin "27") (pinfunction "GPI01_27") (pintype "bidirectional"))
    )
    (net (code "561") (name "unconnected-(U$12-GPI02-Pad28)") (class "Default")
      (node (ref "U$12") (pin "28") (pinfunction "GPI02_28") (pintype "bidirectional"))
    )
    (net (code "562") (name "unconnected-(U$12-GPI03-Pad29)") (class "Default")
      (node (ref "U$12") (pin "29") (pinfunction "GPI03_29") (pintype "bidirectional"))
    )
    (net (code "563") (name "unconnected-(U$12-GPI04-Pad32)") (class "Default")
      (node (ref "U$12") (pin "32") (pinfunction "GPI04_32") (pintype "bidirectional"))
    )
    (net (code "564") (name "unconnected-(U$12-GPI05-Pad33)") (class "Default")
      (node (ref "U$12") (pin "33") (pinfunction "GPI05_33") (pintype "bidirectional"))
    )
    (net (code "565") (name "unconnected-(U$12-ISOMD-Pad40)") (class "Default")
      (node (ref "U$12") (pin "40") (pinfunction "ISOMD_40") (pintype "bidirectional"))
    )
    (net (code "566") (name "unconnected-(U$12-S1-Pad25)") (class "Default")
      (node (ref "U$12") (pin "25") (pinfunction "S1_25") (pintype "bidirectional"))
    )
    (net (code "567") (name "unconnected-(U$12-SCK(IPA)-Pad42)") (class "Default")
      (node (ref "U$12") (pin "42") (pinfunction "SCK(IPA)_42") (pintype "bidirectional"))
    )
    (net (code "568") (name "unconnected-(U$12-SDI(ICMP)-Pad43)") (class "Default")
      (node (ref "U$12") (pin "43") (pinfunction "SDI(ICMP)_43") (pintype "bidirectional"))
    )
    (net (code "569") (name "unconnected-(U$12-SDO(IBIAS)-Pad44)") (class "Default")
      (node (ref "U$12") (pin "44") (pinfunction "SDO(IBIAS)_44") (pintype "bidirectional"))
    )
    (net (code "570") (name "unconnected-(U$12-SWTEN-Pad36)") (class "Default")
      (node (ref "U$12") (pin "36") (pinfunction "SWTEN_36") (pintype "bidirectional"))
    )
    (net (code "571") (name "unconnected-(U$12-V-**-Pad30)") (class "Default")
      (node (ref "U$12") (pin "30") (pinfunction "V-**_30") (pintype "bidirectional"))
    )
    (net (code "572") (name "unconnected-(U$12-V--Pad31)") (class "Default")
      (node (ref "U$12") (pin "31") (pinfunction "V-_31") (pintype "bidirectional"))
    )
    (net (code "573") (name "unconnected-(U$12-VREF1-Pad35)") (class "Default")
      (node (ref "U$12") (pin "35") (pinfunction "VREF1_35") (pintype "bidirectional"))
    )
    (net (code "574") (name "unconnected-(U$12-VREF2-Pad34)") (class "Default")
      (node (ref "U$12") (pin "34") (pinfunction "VREF2_34") (pintype "bidirectional"))
    )
    (net (code "575") (name "unconnected-(U$12-VREG-Pad37)") (class "Default")
      (node (ref "U$12") (pin "37") (pinfunction "VREG_37") (pintype "bidirectional"))
    )
    (net (code "576") (name "unconnected-(U$12-WDT-Pad39)") (class "Default")
      (node (ref "U$12") (pin "39") (pinfunction "WDT_39") (pintype "bidirectional"))
    )
    (net (code "577") (name "unconnected-(U$13-C1-Pad24)") (class "Default")
      (node (ref "U$13") (pin "24") (pinfunction "C1_24") (pintype "bidirectional"))
    )
    (net (code "578") (name "unconnected-(U$13-C2-Pad22)") (class "Default")
      (node (ref "U$13") (pin "22") (pinfunction "C2_22") (pintype "bidirectional"))
    )
    (net (code "579") (name "unconnected-(U$13-C3-Pad20)") (class "Default")
      (node (ref "U$13") (pin "20") (pinfunction "C3_20") (pintype "bidirectional"))
    )
    (net (code "580") (name "unconnected-(U$13-C4-Pad18)") (class "Default")
      (node (ref "U$13") (pin "18") (pinfunction "C4_18") (pintype "bidirectional"))
    )
    (net (code "581") (name "unconnected-(U$13-C5-Pad16)") (class "Default")
      (node (ref "U$13") (pin "16") (pinfunction "C5_16") (pintype "bidirectional"))
    )
    (net (code "582") (name "unconnected-(U$13-C6-Pad14)") (class "Default")
      (node (ref "U$13") (pin "14") (pinfunction "C6_14") (pintype "bidirectional"))
    )
    (net (code "583") (name "unconnected-(U$13-C7-Pad12)") (class "Default")
      (node (ref "U$13") (pin "12") (pinfunction "C7_12") (pintype "bidirectional"))
    )
    (net (code "584") (name "unconnected-(U$13-C8-Pad10)") (class "Default")
      (node (ref "U$13") (pin "10") (pinfunction "C8_10") (pintype "bidirectional"))
    )
    (net (code "585") (name "unconnected-(U$13-C9-Pad8)") (class "Default")
      (node (ref "U$13") (pin "8") (pinfunction "C9_8") (pintype "bidirectional"))
    )
    (net (code "586") (name "unconnected-(U$13-C10-Pad6)") (class "Default")
      (node (ref "U$13") (pin "6") (pinfunction "C10_6") (pintype "bidirectional"))
    )
    (net (code "587") (name "unconnected-(U$13-C11-Pad4)") (class "Default")
      (node (ref "U$13") (pin "4") (pinfunction "C11_4") (pintype "bidirectional"))
    )
    (net (code "588") (name "unconnected-(U$13-C12-Pad2)") (class "Default")
      (node (ref "U$13") (pin "2") (pinfunction "C12_2") (pintype "bidirectional"))
    )
    (net (code "589") (name "unconnected-(U$13-S2-Pad23)") (class "Default")
      (node (ref "U$13") (pin "23") (pinfunction "S2_23") (pintype "bidirectional"))
    )
    (net (code "590") (name "unconnected-(U$13-S3-Pad21)") (class "Default")
      (node (ref "U$13") (pin "21") (pinfunction "S3_21") (pintype "bidirectional"))
    )
    (net (code "591") (name "unconnected-(U$13-S4-Pad19)") (class "Default")
      (node (ref "U$13") (pin "19") (pinfunction "S4_19") (pintype "bidirectional"))
    )
    (net (code "592") (name "unconnected-(U$13-S5-Pad17)") (class "Default")
      (node (ref "U$13") (pin "17") (pinfunction "S5_17") (pintype "bidirectional"))
    )
    (net (code "593") (name "unconnected-(U$13-S6-Pad15)") (class "Default")
      (node (ref "U$13") (pin "15") (pinfunction "S6_15") (pintype "bidirectional"))
    )
    (net (code "594") (name "unconnected-(U$13-S7-Pad13)") (class "Default")
      (node (ref "U$13") (pin "13") (pinfunction "S7_13") (pintype "bidirectional"))
    )
    (net (code "595") (name "unconnected-(U$13-S8-Pad11)") (class "Default")
      (node (ref "U$13") (pin "11") (pinfunction "S8_11") (pintype "bidirectional"))
    )
    (net (code "596") (name "unconnected-(U$13-S9-Pad9)") (class "Default")
      (node (ref "U$13") (pin "9") (pinfunction "S9_9") (pintype "bidirectional"))
    )
    (net (code "597") (name "unconnected-(U$13-S10-Pad7)") (class "Default")
      (node (ref "U$13") (pin "7") (pinfunction "S10_7") (pintype "bidirectional"))
    )
    (net (code "598") (name "unconnected-(U$13-S11-Pad5)") (class "Default")
      (node (ref "U$13") (pin "5") (pinfunction "S11_5") (pintype "bidirectional"))
    )
    (net (code "599") (name "unconnected-(U$13-S12-Pad3)") (class "Default")
      (node (ref "U$13") (pin "3") (pinfunction "S12_3") (pintype "bidirectional"))
    )
    (net (code "600") (name "unconnected-(U$13-V+-Pad1)") (class "Default")
      (node (ref "U$13") (pin "1") (pinfunction "V+_1") (pintype "bidirectional"))
    )
    (net (code "601") (name "unconnected-(U$18-A0-Pad45)") (class "Default")
      (node (ref "U$18") (pin "45") (pinfunction "A0_45") (pintype "bidirectional"))
    )
    (net (code "602") (name "unconnected-(U$18-A1-Pad46)") (class "Default")
      (node (ref "U$18") (pin "46") (pinfunction "A1_46") (pintype "bidirectional"))
    )
    (net (code "603") (name "unconnected-(U$18-A2-Pad47)") (class "Default")
      (node (ref "U$18") (pin "47") (pinfunction "A2_47") (pintype "bidirectional"))
    )
    (net (code "604") (name "unconnected-(U$18-A3-Pad48)") (class "Default")
      (node (ref "U$18") (pin "48") (pinfunction "A3_48") (pintype "bidirectional"))
    )
    (net (code "605") (name "unconnected-(U$18-C0-Pad26)") (class "Default")
      (node (ref "U$18") (pin "26") (pinfunction "C0_26") (pintype "bidirectional"))
    )
    (net (code "606") (name "unconnected-(U$18-CSB(IMA)-Pad41)") (class "Default")
      (node (ref "U$18") (pin "41") (pinfunction "CSB(IMA)_41") (pintype "bidirectional"))
    )
    (net (code "607") (name "unconnected-(U$18-DRIVE-Pad38)") (class "Default")
      (node (ref "U$18") (pin "38") (pinfunction "DRIVE_38") (pintype "bidirectional"))
    )
    (net (code "608") (name "unconnected-(U$18-GPI01-Pad27)") (class "Default")
      (node (ref "U$18") (pin "27") (pinfunction "GPI01_27") (pintype "bidirectional"))
    )
    (net (code "609") (name "unconnected-(U$18-GPI02-Pad28)") (class "Default")
      (node (ref "U$18") (pin "28") (pinfunction "GPI02_28") (pintype "bidirectional"))
    )
    (net (code "610") (name "unconnected-(U$18-GPI03-Pad29)") (class "Default")
      (node (ref "U$18") (pin "29") (pinfunction "GPI03_29") (pintype "bidirectional"))
    )
    (net (code "611") (name "unconnected-(U$18-GPI04-Pad32)") (class "Default")
      (node (ref "U$18") (pin "32") (pinfunction "GPI04_32") (pintype "bidirectional"))
    )
    (net (code "612") (name "unconnected-(U$18-GPI05-Pad33)") (class "Default")
      (node (ref "U$18") (pin "33") (pinfunction "GPI05_33") (pintype "bidirectional"))
    )
    (net (code "613") (name "unconnected-(U$18-ISOMD-Pad40)") (class "Default")
      (node (ref "U$18") (pin "40") (pinfunction "ISOMD_40") (pintype "bidirectional"))
    )
    (net (code "614") (name "unconnected-(U$18-S1-Pad25)") (class "Default")
      (node (ref "U$18") (pin "25") (pinfunction "S1_25") (pintype "bidirectional"))
    )
    (net (code "615") (name "unconnected-(U$18-SCK(IPA)-Pad42)") (class "Default")
      (node (ref "U$18") (pin "42") (pinfunction "SCK(IPA)_42") (pintype "bidirectional"))
    )
    (net (code "616") (name "unconnected-(U$18-SDI(ICMP)-Pad43)") (class "Default")
      (node (ref "U$18") (pin "43") (pinfunction "SDI(ICMP)_43") (pintype "bidirectional"))
    )
    (net (code "617") (name "unconnected-(U$18-SDO(IBIAS)-Pad44)") (class "Default")
      (node (ref "U$18") (pin "44") (pinfunction "SDO(IBIAS)_44") (pintype "bidirectional"))
    )
    (net (code "618") (name "unconnected-(U$18-SWTEN-Pad36)") (class "Default")
      (node (ref "U$18") (pin "36") (pinfunction "SWTEN_36") (pintype "bidirectional"))
    )
    (net (code "619") (name "unconnected-(U$18-V-**-Pad30)") (class "Default")
      (node (ref "U$18") (pin "30") (pinfunction "V-**_30") (pintype "bidirectional"))
    )
    (net (code "620") (name "unconnected-(U$18-V--Pad31)") (class "Default")
      (node (ref "U$18") (pin "31") (pinfunction "V-_31") (pintype "bidirectional"))
    )
    (net (code "621") (name "unconnected-(U$18-VREF1-Pad35)") (class "Default")
      (node (ref "U$18") (pin "35") (pinfunction "VREF1_35") (pintype "bidirectional"))
    )
    (net (code "622") (name "unconnected-(U$18-VREF2-Pad34)") (class "Default")
      (node (ref "U$18") (pin "34") (pinfunction "VREF2_34") (pintype "bidirectional"))
    )
    (net (code "623") (name "unconnected-(U$18-VREG-Pad37)") (class "Default")
      (node (ref "U$18") (pin "37") (pinfunction "VREG_37") (pintype "bidirectional"))
    )
    (net (code "624") (name "unconnected-(U$18-WDT-Pad39)") (class "Default")
      (node (ref "U$18") (pin "39") (pinfunction "WDT_39") (pintype "bidirectional"))
    )
    (net (code "625") (name "unconnected-(U$19-C1-Pad24)") (class "Default")
      (node (ref "U$19") (pin "24") (pinfunction "C1_24") (pintype "bidirectional"))
    )
    (net (code "626") (name "unconnected-(U$19-C2-Pad22)") (class "Default")
      (node (ref "U$19") (pin "22") (pinfunction "C2_22") (pintype "bidirectional"))
    )
    (net (code "627") (name "unconnected-(U$19-C3-Pad20)") (class "Default")
      (node (ref "U$19") (pin "20") (pinfunction "C3_20") (pintype "bidirectional"))
    )
    (net (code "628") (name "unconnected-(U$19-C4-Pad18)") (class "Default")
      (node (ref "U$19") (pin "18") (pinfunction "C4_18") (pintype "bidirectional"))
    )
    (net (code "629") (name "unconnected-(U$19-C5-Pad16)") (class "Default")
      (node (ref "U$19") (pin "16") (pinfunction "C5_16") (pintype "bidirectional"))
    )
    (net (code "630") (name "unconnected-(U$19-C6-Pad14)") (class "Default")
      (node (ref "U$19") (pin "14") (pinfunction "C6_14") (pintype "bidirectional"))
    )
    (net (code "631") (name "unconnected-(U$19-C7-Pad12)") (class "Default")
      (node (ref "U$19") (pin "12") (pinfunction "C7_12") (pintype "bidirectional"))
    )
    (net (code "632") (name "unconnected-(U$19-C8-Pad10)") (class "Default")
      (node (ref "U$19") (pin "10") (pinfunction "C8_10") (pintype "bidirectional"))
    )
    (net (code "633") (name "unconnected-(U$19-C9-Pad8)") (class "Default")
      (node (ref "U$19") (pin "8") (pinfunction "C9_8") (pintype "bidirectional"))
    )
    (net (code "634") (name "unconnected-(U$19-C10-Pad6)") (class "Default")
      (node (ref "U$19") (pin "6") (pinfunction "C10_6") (pintype "bidirectional"))
    )
    (net (code "635") (name "unconnected-(U$19-C11-Pad4)") (class "Default")
      (node (ref "U$19") (pin "4") (pinfunction "C11_4") (pintype "bidirectional"))
    )
    (net (code "636") (name "unconnected-(U$19-C12-Pad2)") (class "Default")
      (node (ref "U$19") (pin "2") (pinfunction "C12_2") (pintype "bidirectional"))
    )
    (net (code "637") (name "unconnected-(U$19-S2-Pad23)") (class "Default")
      (node (ref "U$19") (pin "23") (pinfunction "S2_23") (pintype "bidirectional"))
    )
    (net (code "638") (name "unconnected-(U$19-S3-Pad21)") (class "Default")
      (node (ref "U$19") (pin "21") (pinfunction "S3_21") (pintype "bidirectional"))
    )
    (net (code "639") (name "unconnected-(U$19-S4-Pad19)") (class "Default")
      (node (ref "U$19") (pin "19") (pinfunction "S4_19") (pintype "bidirectional"))
    )
    (net (code "640") (name "unconnected-(U$19-S5-Pad17)") (class "Default")
      (node (ref "U$19") (pin "17") (pinfunction "S5_17") (pintype "bidirectional"))
    )
    (net (code "641") (name "unconnected-(U$19-S6-Pad15)") (class "Default")
      (node (ref "U$19") (pin "15") (pinfunction "S6_15") (pintype "bidirectional"))
    )
    (net (code "642") (name "unconnected-(U$19-S7-Pad13)") (class "Default")
      (node (ref "U$19") (pin "13") (pinfunction "S7_13") (pintype "bidirectional"))
    )
    (net (code "643") (name "unconnected-(U$19-S8-Pad11)") (class "Default")
      (node (ref "U$19") (pin "11") (pinfunction "S8_11") (pintype "bidirectional"))
    )
    (net (code "644") (name "unconnected-(U$19-S9-Pad9)") (class "Default")
      (node (ref "U$19") (pin "9") (pinfunction "S9_9") (pintype "bidirectional"))
    )
    (net (code "645") (name "unconnected-(U$19-S10-Pad7)") (class "Default")
      (node (ref "U$19") (pin "7") (pinfunction "S10_7") (pintype "bidirectional"))
    )
    (net (code "646") (name "unconnected-(U$19-S11-Pad5)") (class "Default")
      (node (ref "U$19") (pin "5") (pinfunction "S11_5") (pintype "bidirectional"))
    )
    (net (code "647") (name "unconnected-(U$19-S12-Pad3)") (class "Default")
      (node (ref "U$19") (pin "3") (pinfunction "S12_3") (pintype "bidirectional"))
    )
    (net (code "648") (name "unconnected-(U$19-V+-Pad1)") (class "Default")
      (node (ref "U$19") (pin "1") (pinfunction "V+_1") (pintype "bidirectional"))
    )
    (net (code "649") (name "unconnected-(U$24-A0-Pad45)") (class "Default")
      (node (ref "U$24") (pin "45") (pinfunction "A0_45") (pintype "bidirectional"))
    )
    (net (code "650") (name "unconnected-(U$24-A1-Pad46)") (class "Default")
      (node (ref "U$24") (pin "46") (pinfunction "A1_46") (pintype "bidirectional"))
    )
    (net (code "651") (name "unconnected-(U$24-A2-Pad47)") (class "Default")
      (node (ref "U$24") (pin "47") (pinfunction "A2_47") (pintype "bidirectional"))
    )
    (net (code "652") (name "unconnected-(U$24-A3-Pad48)") (class "Default")
      (node (ref "U$24") (pin "48") (pinfunction "A3_48") (pintype "bidirectional"))
    )
    (net (code "653") (name "unconnected-(U$24-C0-Pad26)") (class "Default")
      (node (ref "U$24") (pin "26") (pinfunction "C0_26") (pintype "bidirectional"))
    )
    (net (code "654") (name "unconnected-(U$24-CSB(IMA)-Pad41)") (class "Default")
      (node (ref "U$24") (pin "41") (pinfunction "CSB(IMA)_41") (pintype "bidirectional"))
    )
    (net (code "655") (name "unconnected-(U$24-DRIVE-Pad38)") (class "Default")
      (node (ref "U$24") (pin "38") (pinfunction "DRIVE_38") (pintype "bidirectional"))
    )
    (net (code "656") (name "unconnected-(U$24-GPI01-Pad27)") (class "Default")
      (node (ref "U$24") (pin "27") (pinfunction "GPI01_27") (pintype "bidirectional"))
    )
    (net (code "657") (name "unconnected-(U$24-GPI02-Pad28)") (class "Default")
      (node (ref "U$24") (pin "28") (pinfunction "GPI02_28") (pintype "bidirectional"))
    )
    (net (code "658") (name "unconnected-(U$24-GPI03-Pad29)") (class "Default")
      (node (ref "U$24") (pin "29") (pinfunction "GPI03_29") (pintype "bidirectional"))
    )
    (net (code "659") (name "unconnected-(U$24-GPI04-Pad32)") (class "Default")
      (node (ref "U$24") (pin "32") (pinfunction "GPI04_32") (pintype "bidirectional"))
    )
    (net (code "660") (name "unconnected-(U$24-GPI05-Pad33)") (class "Default")
      (node (ref "U$24") (pin "33") (pinfunction "GPI05_33") (pintype "bidirectional"))
    )
    (net (code "661") (name "unconnected-(U$24-ISOMD-Pad40)") (class "Default")
      (node (ref "U$24") (pin "40") (pinfunction "ISOMD_40") (pintype "bidirectional"))
    )
    (net (code "662") (name "unconnected-(U$24-S1-Pad25)") (class "Default")
      (node (ref "U$24") (pin "25") (pinfunction "S1_25") (pintype "bidirectional"))
    )
    (net (code "663") (name "unconnected-(U$24-SCK(IPA)-Pad42)") (class "Default")
      (node (ref "U$24") (pin "42") (pinfunction "SCK(IPA)_42") (pintype "bidirectional"))
    )
    (net (code "664") (name "unconnected-(U$24-SDI(ICMP)-Pad43)") (class "Default")
      (node (ref "U$24") (pin "43") (pinfunction "SDI(ICMP)_43") (pintype "bidirectional"))
    )
    (net (code "665") (name "unconnected-(U$24-SDO(IBIAS)-Pad44)") (class "Default")
      (node (ref "U$24") (pin "44") (pinfunction "SDO(IBIAS)_44") (pintype "bidirectional"))
    )
    (net (code "666") (name "unconnected-(U$24-SWTEN-Pad36)") (class "Default")
      (node (ref "U$24") (pin "36") (pinfunction "SWTEN_36") (pintype "bidirectional"))
    )
    (net (code "667") (name "unconnected-(U$24-V-**-Pad30)") (class "Default")
      (node (ref "U$24") (pin "30") (pinfunction "V-**_30") (pintype "bidirectional"))
    )
    (net (code "668") (name "unconnected-(U$24-V--Pad31)") (class "Default")
      (node (ref "U$24") (pin "31") (pinfunction "V-_31") (pintype "bidirectional"))
    )
    (net (code "669") (name "unconnected-(U$24-VREF1-Pad35)") (class "Default")
      (node (ref "U$24") (pin "35") (pinfunction "VREF1_35") (pintype "bidirectional"))
    )
    (net (code "670") (name "unconnected-(U$24-VREF2-Pad34)") (class "Default")
      (node (ref "U$24") (pin "34") (pinfunction "VREF2_34") (pintype "bidirectional"))
    )
    (net (code "671") (name "unconnected-(U$24-VREG-Pad37)") (class "Default")
      (node (ref "U$24") (pin "37") (pinfunction "VREG_37") (pintype "bidirectional"))
    )
    (net (code "672") (name "unconnected-(U$24-WDT-Pad39)") (class "Default")
      (node (ref "U$24") (pin "39") (pinfunction "WDT_39") (pintype "bidirectional"))
    )
    (net (code "673") (name "unconnected-(U$25-S-PadP$1)") (class "Default")
      (node (ref "U$25") (pin "P$1") (pinfunction "S_P$1") (pintype "passive"))
    )
    (net (code "674") (name "unconnected-(U$26-S-PadP$1)") (class "Default")
      (node (ref "U$26") (pin "P$1") (pinfunction "S_P$1") (pintype "passive"))
    )
    (net (code "675") (name "unconnected-(U$27-S-PadP$1)") (class "Default")
      (node (ref "U$27") (pin "P$1") (pinfunction "S_P$1") (pintype "passive"))
    )
    (net (code "676") (name "unconnected-(U$28-S-PadP$1)") (class "Default")
      (node (ref "U$28") (pin "P$1") (pinfunction "S_P$1") (pintype "passive"))
    )
    (net (code "677") (name "unconnected-(U$29-S-PadP$1)") (class "Default")
      (node (ref "U$29") (pin "P$1") (pinfunction "S_P$1") (pintype "passive"))
    )
    (net (code "678") (name "unconnected-(U$30-S-PadP$1)") (class "Default")
      (node (ref "U$30") (pin "P$1") (pinfunction "S_P$1") (pintype "passive"))
    )
    (net (code "679") (name "unconnected-(U$31-S-PadP$1)") (class "Default")
      (node (ref "U$31") (pin "P$1") (pinfunction "S_P$1") (pintype "passive"))
    )
    (net (code "680") (name "unconnected-(U$32-S-PadP$1)") (class "Default")
      (node (ref "U$32") (pin "P$1") (pinfunction "S_P$1") (pintype "passive"))
    )
    (net (code "681") (name "unconnected-(U$33-S-PadP$1)") (class "Default")
      (node (ref "U$33") (pin "P$1") (pinfunction "S_P$1") (pintype "passive"))
    )
  )
)
